# Shruthi-Digital-XT-v03.net
KiCad netlist of a schematic drawn in EAGLE
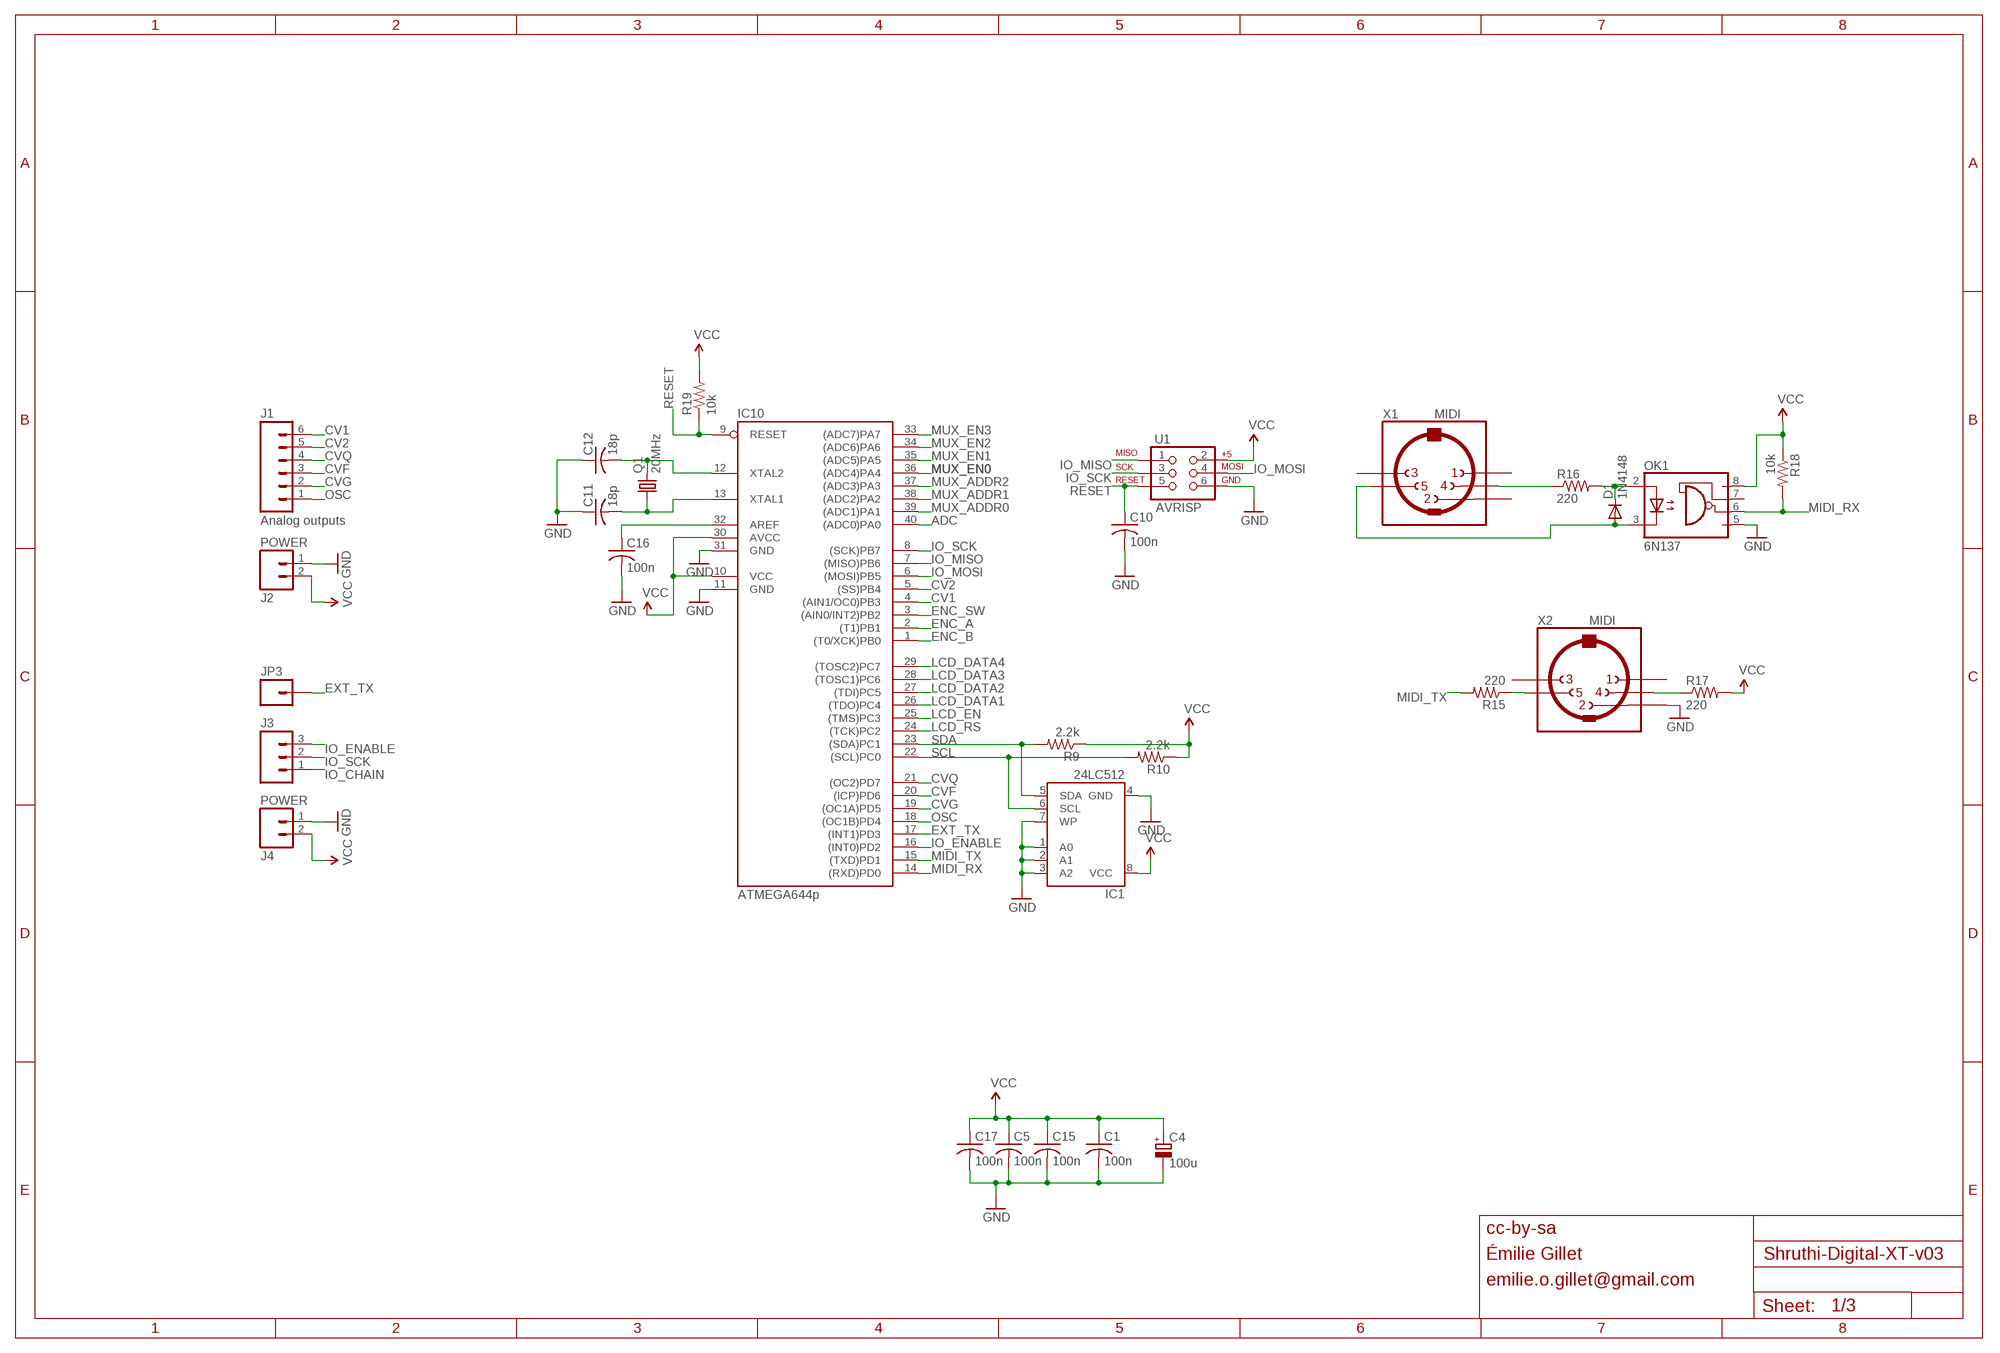
[diagram p0: schematic, sheet 1]
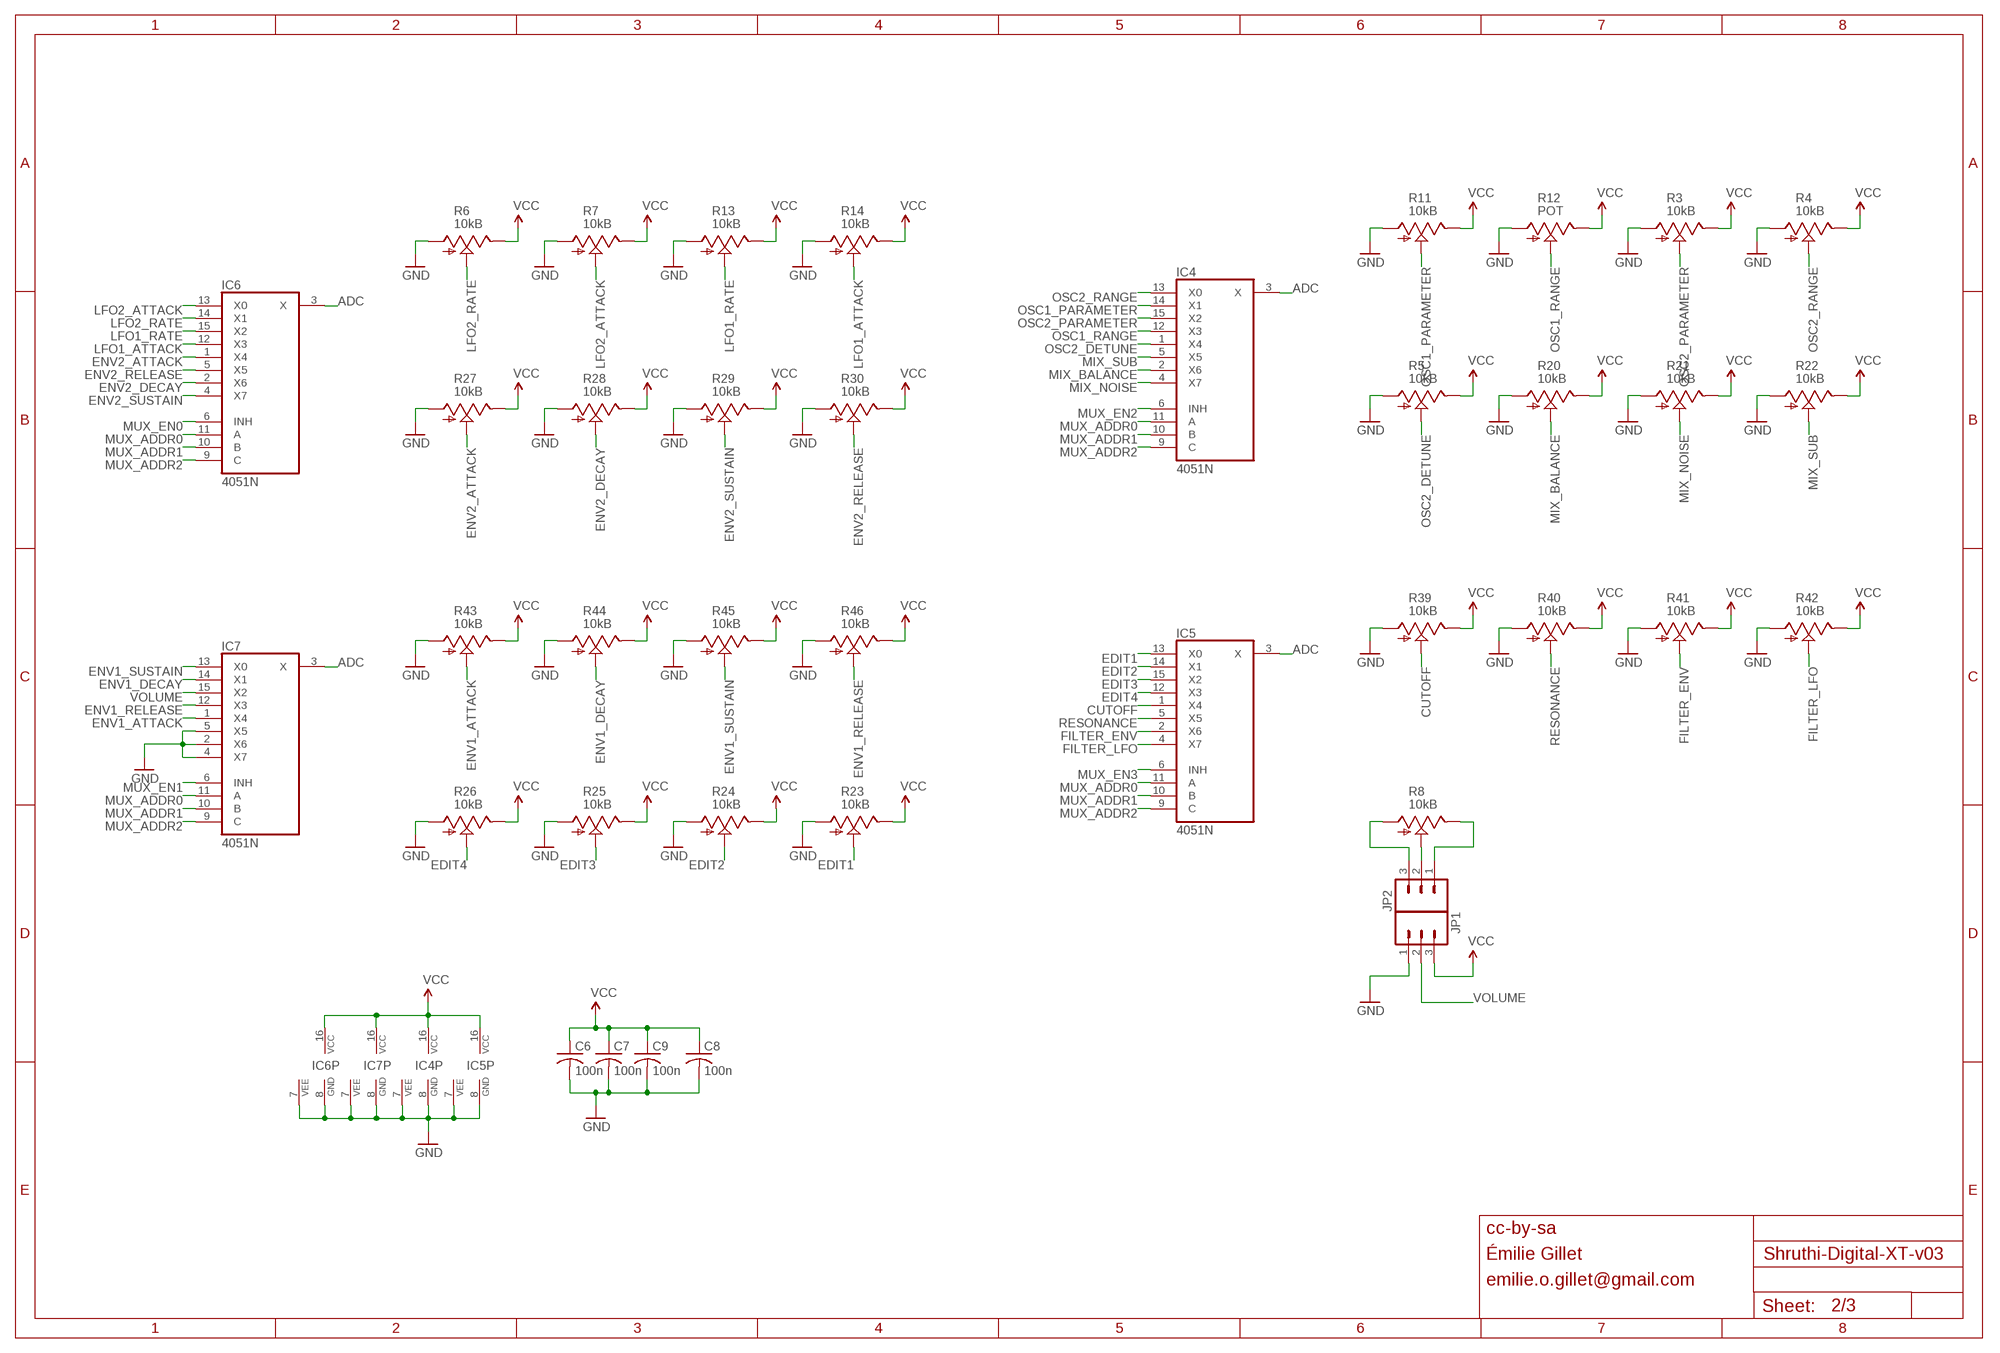
[diagram p1: schematic, sheet 2]
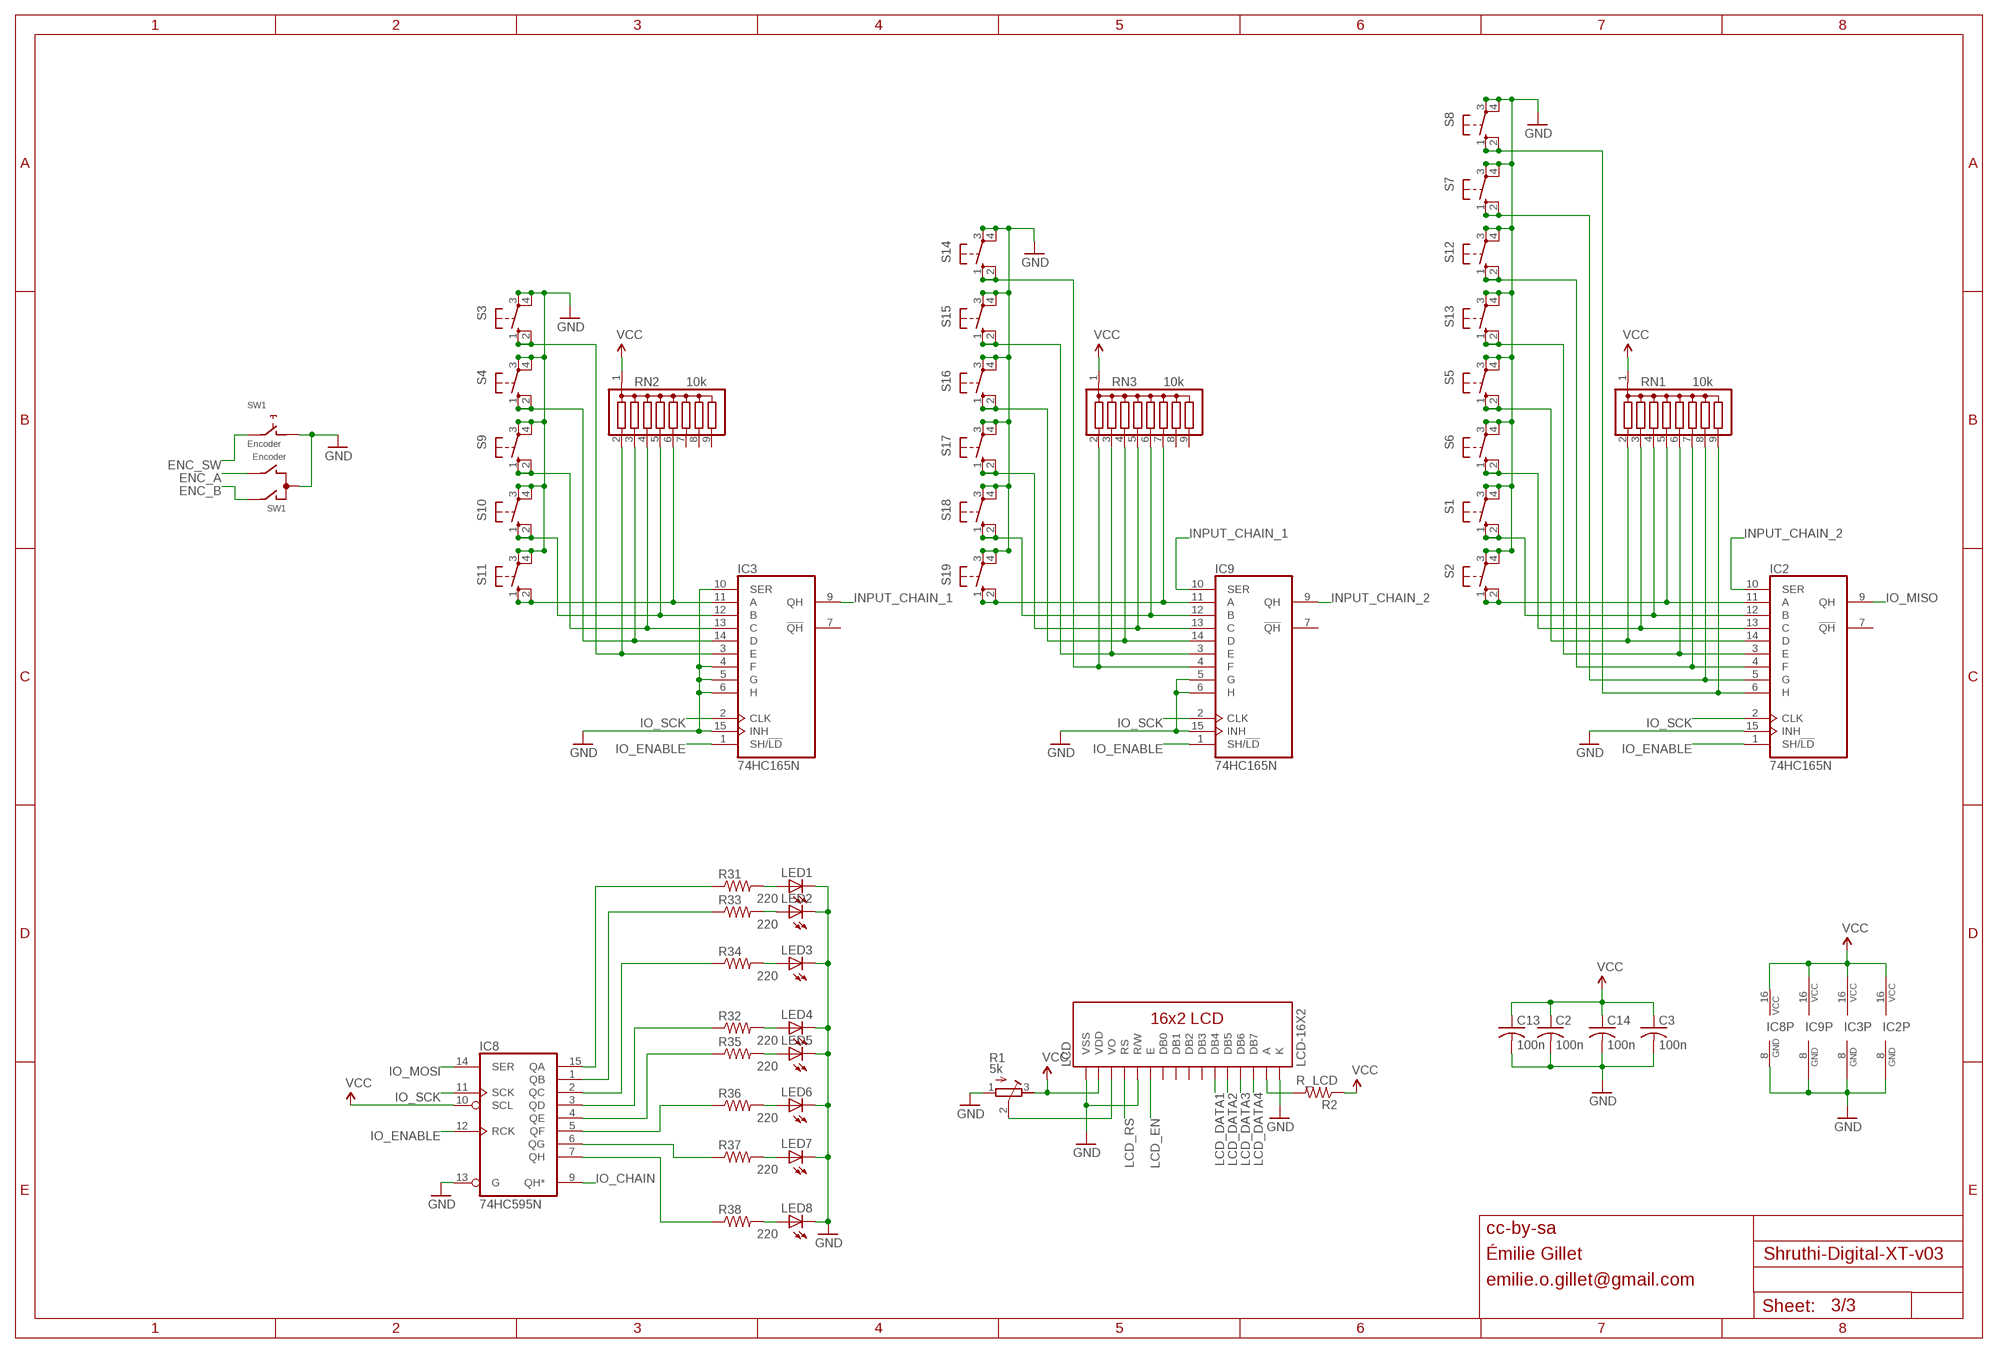
[diagram p2: schematic, sheet 3]

(export (version "E")
  (design (tool "Eeschema 10.0.6"))
  (components
    (comp (ref "C1")
      (value "100n")
      (footprint "eagle-import:C025-024X044")
      (libsource (lib "eagle-import") (part "C-US025-024X044"))
    )
    (comp (ref "C4")
      (value "100u")
      (footprint "eagle-import:E2,5-7")
      (libsource (lib "eagle-import") (part "CPOL-EUE2.5-7"))
    )
    (comp (ref "C5")
      (value "100n")
      (footprint "eagle-import:C025-024X044")
      (libsource (lib "eagle-import") (part "C-US025-024X044"))
    )
    (comp (ref "C10")
      (value "100n")
      (footprint "eagle-import:C025-024X044")
      (libsource (lib "eagle-import") (part "C-US025-024X044"))
    )
    (comp (ref "C11")
      (value "18p")
      (footprint "eagle-import:C025-024X044")
      (libsource (lib "eagle-import") (part "C-US025-024X044"))
    )
    (comp (ref "C12")
      (value "18p")
      (footprint "eagle-import:C025-024X044")
      (libsource (lib "eagle-import") (part "C-US025-024X044"))
    )
    (comp (ref "C15")
      (value "100n")
      (footprint "eagle-import:C025-024X044")
      (libsource (lib "eagle-import") (part "C-US025-024X044"))
    )
    (comp (ref "C16")
      (value "100n")
      (footprint "eagle-import:C025-024X044")
      (libsource (lib "eagle-import") (part "C-US025-024X044"))
    )
    (comp (ref "C17")
      (value "100n")
      (footprint "eagle-import:C025-024X044")
      (libsource (lib "eagle-import") (part "C-US025-024X044"))
    )
    (comp (ref "D1")
      (value "1N4148")
      (footprint "eagle-import:D-5")
      (libsource (lib "eagle-import") (part "DIODE-D-5"))
    )
    (comp (ref "IC1")
      (value "24LC512")
      (footprint "eagle-import:DIL08")
      (libsource (lib "eagle-import") (part "AT24CP"))
    )
    (comp (ref "IC10")
      (value "ATMEGA644p")
      (footprint "eagle-import:DIL40")
      (libsource (lib "eagle-import") (part "MEGA16-P"))
    )
    (comp (ref "J1")
      (value "M06SIP")
      (footprint "eagle-import:1X06")
      (libsource (lib "eagle-import") (part "M06SIP"))
    )
    (comp (ref "J2")
      (value "POWER")
      (footprint "eagle-import:1X02")
      (libsource (lib "eagle-import") (part "M02PTH"))
    )
    (comp (ref "J3")
      (value "M03PTH")
      (footprint "eagle-import:1X03")
      (libsource (lib "eagle-import") (part "M03PTH"))
    )
    (comp (ref "J4")
      (value "POWER")
      (footprint "eagle-import:1X02")
      (libsource (lib "eagle-import") (part "M02PTH"))
    )
    (comp (ref "JP3")
      (value "M01PTH")
      (footprint "eagle-import:1X01")
      (libsource (lib "eagle-import") (part "M01PTH"))
    )
    (comp (ref "OK1")
      (value "6N137")
      (footprint "eagle-import:DIL08")
      (libsource (lib "eagle-import") (part "6N137"))
    )
    (comp (ref "Q1")
      (value "20MHz")
      (footprint "eagle-import:HC49U-V")
      (libsource (lib "eagle-import") (part "CRYSTALHC49U-V"))
    )
    (comp (ref "R9")
      (value "2.2k")
      (footprint "eagle-import:0204_7")
      (libsource (lib "eagle-import") (part "R-US_0204/7"))
    )
    (comp (ref "R10")
      (value "2.2k")
      (footprint "eagle-import:0204_7")
      (libsource (lib "eagle-import") (part "R-US_0204/7"))
    )
    (comp (ref "R15")
      (value "220")
      (footprint "eagle-import:0204_7")
      (libsource (lib "eagle-import") (part "R-US_0204/7"))
    )
    (comp (ref "R16")
      (value "220")
      (footprint "eagle-import:0204_7")
      (libsource (lib "eagle-import") (part "R-US_0204/7"))
    )
    (comp (ref "R17")
      (value "220")
      (footprint "eagle-import:0204_7")
      (libsource (lib "eagle-import") (part "R-US_0204/7"))
    )
    (comp (ref "R18")
      (value "10k")
      (footprint "eagle-import:0204_7")
      (libsource (lib "eagle-import") (part "R-US_0204/7"))
    )
    (comp (ref "R19")
      (value "10k")
      (footprint "eagle-import:0204_7")
      (libsource (lib "eagle-import") (part "R-US_0204/7"))
    )
    (comp (ref "U1")
      (value "AVRISP")
      (footprint "eagle-import:2X3")
      (libsource (lib "eagle-import") (part "AVR_SPI_PRG_6PTH"))
    )
    (comp (ref "X1")
      (value "MIDI")
      (footprint "eagle-import:MAB5SH")
      (libsource (lib "eagle-import") (part "MAB5SH"))
    )
    (comp (ref "X2")
      (value "MIDI")
      (footprint "eagle-import:MAB5SH")
      (libsource (lib "eagle-import") (part "MAB5SH"))
    )
    (comp (ref "C2")
      (value "100n")
      (footprint "eagle-import:C025-024X044")
      (libsource (lib "eagle-import") (part "C-US025-024X044"))
    )
    (comp (ref "C3")
      (value "100n")
      (footprint "eagle-import:C025-024X044")
      (libsource (lib "eagle-import") (part "C-US025-024X044"))
    )
    (comp (ref "C13")
      (value "100n")
      (footprint "eagle-import:C025-024X044")
      (libsource (lib "eagle-import") (part "C-US025-024X044"))
    )
    (comp (ref "C14")
      (value "100n")
      (footprint "eagle-import:C025-024X044")
      (libsource (lib "eagle-import") (part "C-US025-024X044"))
    )
    (comp (ref "IC2")
      (value "74HC165N")
      (footprint "eagle-import:DIL16")
      (libsource (lib "eagle-import") (part "74165NLS"))
    )
    (comp (ref "IC3")
      (value "74HC165N")
      (footprint "eagle-import:DIL16")
      (libsource (lib "eagle-import") (part "74165NLS"))
    )
    (comp (ref "IC8")
      (value "74HC595N")
      (footprint "eagle-import:DIL16")
      (libsource (lib "eagle-import") (part "74595NHC"))
    )
    (comp (ref "IC9")
      (value "74HC165N")
      (footprint "eagle-import:DIL16")
      (libsource (lib "eagle-import") (part "74165NLS"))
    )
    (comp (ref "LCD")
      (value "LCD-16X2")
      (footprint "eagle-import:LCD-16X2")
      (libsource (lib "eagle-import") (part "LCD-16X2"))
    )
    (comp (ref "LED1")
      (value "LED3MM")
      (footprint "eagle-import:LED3MM")
      (libsource (lib "eagle-import") (part "LED3MM"))
    )
    (comp (ref "LED2")
      (value "LED3MM")
      (footprint "eagle-import:LED3MM")
      (libsource (lib "eagle-import") (part "LED3MM"))
    )
    (comp (ref "LED3")
      (value "LED3MM")
      (footprint "eagle-import:LED3MM")
      (libsource (lib "eagle-import") (part "LED3MM"))
    )
    (comp (ref "LED4")
      (value "LED3MM")
      (footprint "eagle-import:LED3MM")
      (libsource (lib "eagle-import") (part "LED3MM"))
    )
    (comp (ref "LED5")
      (value "LED3MM")
      (footprint "eagle-import:LED3MM")
      (libsource (lib "eagle-import") (part "LED3MM"))
    )
    (comp (ref "LED6")
      (value "LED3MM")
      (footprint "eagle-import:LED3MM")
      (libsource (lib "eagle-import") (part "LED3MM"))
    )
    (comp (ref "LED7")
      (value "LED3MM")
      (footprint "eagle-import:LED3MM")
      (libsource (lib "eagle-import") (part "LED3MM"))
    )
    (comp (ref "LED8")
      (value "LED3MM")
      (footprint "eagle-import:LED3MM")
      (libsource (lib "eagle-import") (part "LED3MM"))
    )
    (comp (ref "R1")
      (value "5k")
      (footprint "eagle-import:RTRIM3339P")
      (libsource (lib "eagle-import") (part "R-TRIMM3339P"))
    )
    (comp (ref "R2")
      (value "R_LCD")
      (footprint "eagle-import:0204_7")
      (libsource (lib "eagle-import") (part "R-US_0204/7"))
    )
    (comp (ref "R31")
      (value "220")
      (footprint "eagle-import:0204_7")
      (libsource (lib "eagle-import") (part "R-US_0204/7"))
    )
    (comp (ref "R32")
      (value "220")
      (footprint "eagle-import:0204_7")
      (libsource (lib "eagle-import") (part "R-US_0204/7"))
    )
    (comp (ref "R33")
      (value "220")
      (footprint "eagle-import:0204_7")
      (libsource (lib "eagle-import") (part "R-US_0204/7"))
    )
    (comp (ref "R34")
      (value "220")
      (footprint "eagle-import:0204_7")
      (libsource (lib "eagle-import") (part "R-US_0204/7"))
    )
    (comp (ref "R35")
      (value "220")
      (footprint "eagle-import:0204_7")
      (libsource (lib "eagle-import") (part "R-US_0204/7"))
    )
    (comp (ref "R36")
      (value "220")
      (footprint "eagle-import:0204_7")
      (libsource (lib "eagle-import") (part "R-US_0204/7"))
    )
    (comp (ref "R37")
      (value "220")
      (footprint "eagle-import:0204_7")
      (libsource (lib "eagle-import") (part "R-US_0204/7"))
    )
    (comp (ref "R38")
      (value "220")
      (footprint "eagle-import:0204_7")
      (libsource (lib "eagle-import") (part "R-US_0204/7"))
    )
    (comp (ref "RN1")
      (value "10k")
      (footprint "eagle-import:SIL9")
      (libsource (lib "eagle-import") (part "G08R"))
    )
    (comp (ref "RN2")
      (value "10k")
      (footprint "eagle-import:SIL9")
      (libsource (lib "eagle-import") (part "G08R"))
    )
    (comp (ref "RN3")
      (value "10k")
      (footprint "eagle-import:SIL9")
      (libsource (lib "eagle-import") (part "G08R"))
    )
    (comp (ref "S1")
      (value "40-XX")
      (footprint "eagle-import:B3F-40XX")
      (libsource (lib "eagle-import") (part "40-XX"))
    )
    (comp (ref "S2")
      (value "40-XX")
      (footprint "eagle-import:B3F-40XX")
      (libsource (lib "eagle-import") (part "40-XX"))
    )
    (comp (ref "S3")
      (value "40-XX")
      (footprint "eagle-import:B3F-40XX")
      (libsource (lib "eagle-import") (part "40-XX"))
    )
    (comp (ref "S4")
      (value "40-XX")
      (footprint "eagle-import:B3F-40XX")
      (libsource (lib "eagle-import") (part "40-XX"))
    )
    (comp (ref "S5")
      (value "40-XX")
      (footprint "eagle-import:B3F-40XX")
      (libsource (lib "eagle-import") (part "40-XX"))
    )
    (comp (ref "S6")
      (value "40-XX")
      (footprint "eagle-import:B3F-40XX")
      (libsource (lib "eagle-import") (part "40-XX"))
    )
    (comp (ref "S7")
      (value "40-XX")
      (footprint "eagle-import:B3F-40XX")
      (libsource (lib "eagle-import") (part "40-XX"))
    )
    (comp (ref "S8")
      (value "40-XX")
      (footprint "eagle-import:B3F-40XX")
      (libsource (lib "eagle-import") (part "40-XX"))
    )
    (comp (ref "S9")
      (value "40-XX")
      (footprint "eagle-import:B3F-40XX")
      (libsource (lib "eagle-import") (part "40-XX"))
    )
    (comp (ref "S10")
      (value "40-XX")
      (footprint "eagle-import:B3F-40XX")
      (libsource (lib "eagle-import") (part "40-XX"))
    )
    (comp (ref "S11")
      (value "40-XX")
      (footprint "eagle-import:B3F-40XX")
      (libsource (lib "eagle-import") (part "40-XX"))
    )
    (comp (ref "S12")
      (value "40-XX")
      (footprint "eagle-import:B3F-40XX")
      (libsource (lib "eagle-import") (part "40-XX"))
    )
    (comp (ref "S13")
      (value "40-XX")
      (footprint "eagle-import:B3F-40XX")
      (libsource (lib "eagle-import") (part "40-XX"))
    )
    (comp (ref "S14")
      (value "40-XX")
      (footprint "eagle-import:B3F-40XX")
      (libsource (lib "eagle-import") (part "40-XX"))
    )
    (comp (ref "S15")
      (value "40-XX")
      (footprint "eagle-import:B3F-40XX")
      (libsource (lib "eagle-import") (part "40-XX"))
    )
    (comp (ref "S16")
      (value "40-XX")
      (footprint "eagle-import:B3F-40XX")
      (libsource (lib "eagle-import") (part "40-XX"))
    )
    (comp (ref "S17")
      (value "40-XX")
      (footprint "eagle-import:B3F-40XX")
      (libsource (lib "eagle-import") (part "40-XX"))
    )
    (comp (ref "S18")
      (value "40-XX")
      (footprint "eagle-import:B3F-40XX")
      (libsource (lib "eagle-import") (part "40-XX"))
    )
    (comp (ref "S19")
      (value "40-XX")
      (footprint "eagle-import:B3F-40XX")
      (libsource (lib "eagle-import") (part "40-XX"))
    )
    (comp (ref "SW1")
      (value "Encoder")
      (footprint "eagle-import:ALPS_EC12E_SW")
      (libsource (lib "eagle-import") (part "EC12E_SW"))
    )
    (comp (ref "C6")
      (value "100n")
      (footprint "eagle-import:C025-024X044")
      (libsource (lib "eagle-import") (part "C-US025-024X044"))
    )
    (comp (ref "C7")
      (value "100n")
      (footprint "eagle-import:C025-024X044")
      (libsource (lib "eagle-import") (part "C-US025-024X044"))
    )
    (comp (ref "C8")
      (value "100n")
      (footprint "eagle-import:C025-024X044")
      (libsource (lib "eagle-import") (part "C-US025-024X044"))
    )
    (comp (ref "C9")
      (value "100n")
      (footprint "eagle-import:C025-024X044")
      (libsource (lib "eagle-import") (part "C-US025-024X044"))
    )
    (comp (ref "IC4")
      (value "4051N")
      (footprint "eagle-import:DIL16")
      (libsource (lib "eagle-import") (part "4051N"))
    )
    (comp (ref "IC5")
      (value "4051N")
      (footprint "eagle-import:DIL16")
      (libsource (lib "eagle-import") (part "4051N"))
    )
    (comp (ref "IC6")
      (value "4051N")
      (footprint "eagle-import:DIL16")
      (libsource (lib "eagle-import") (part "4051N"))
    )
    (comp (ref "IC7")
      (value "4051N")
      (footprint "eagle-import:DIL16")
      (libsource (lib "eagle-import") (part "4051N"))
    )
    (comp (ref "JP1")
      (value "M03PTH")
      (footprint "eagle-import:1X03")
      (libsource (lib "eagle-import") (part "M03PTH"))
    )
    (comp (ref "JP2")
      (value "M03PTH")
      (footprint "eagle-import:1X03")
      (libsource (lib "eagle-import") (part "M03PTH"))
    )
    (comp (ref "R3")
      (value "10kB")
      (footprint "eagle-import:ALPS_POT_VERTICAL")
      (libsource (lib "eagle-import") (part "POT_USVERTICAL"))
    )
    (comp (ref "R4")
      (value "10kB")
      (footprint "eagle-import:ALPS_POT_VERTICAL")
      (libsource (lib "eagle-import") (part "POT_USVERTICAL"))
    )
    (comp (ref "R5")
      (value "10kB")
      (footprint "eagle-import:ALPS_POT_VERTICAL")
      (libsource (lib "eagle-import") (part "POT_USVERTICAL"))
    )
    (comp (ref "R6")
      (value "10kB")
      (footprint "eagle-import:ALPS_POT_VERTICAL")
      (libsource (lib "eagle-import") (part "POT_USVERTICAL"))
    )
    (comp (ref "R7")
      (value "10kB")
      (footprint "eagle-import:ALPS_POT_VERTICAL")
      (libsource (lib "eagle-import") (part "POT_USVERTICAL"))
    )
    (comp (ref "R8")
      (value "10kB")
      (footprint "eagle-import:ALPS_POT_VERTICAL")
      (libsource (lib "eagle-import") (part "POT_USVERTICAL"))
    )
    (comp (ref "R11")
      (value "10kB")
      (footprint "eagle-import:ALPS_POT_VERTICAL")
      (libsource (lib "eagle-import") (part "POT_USVERTICAL"))
    )
    (comp (ref "R12")
      (value "POT")
      (footprint "eagle-import:ALPS_POT_VERTICAL")
      (libsource (lib "eagle-import") (part "POT_USVERTICAL"))
    )
    (comp (ref "R13")
      (value "10kB")
      (footprint "eagle-import:ALPS_POT_VERTICAL")
      (libsource (lib "eagle-import") (part "POT_USVERTICAL"))
    )
    (comp (ref "R14")
      (value "10kB")
      (footprint "eagle-import:ALPS_POT_VERTICAL")
      (libsource (lib "eagle-import") (part "POT_USVERTICAL"))
    )
    (comp (ref "R20")
      (value "10kB")
      (footprint "eagle-import:ALPS_POT_VERTICAL")
      (libsource (lib "eagle-import") (part "POT_USVERTICAL"))
    )
    (comp (ref "R21")
      (value "10kB")
      (footprint "eagle-import:ALPS_POT_VERTICAL")
      (libsource (lib "eagle-import") (part "POT_USVERTICAL"))
    )
    (comp (ref "R22")
      (value "10kB")
      (footprint "eagle-import:ALPS_POT_VERTICAL")
      (libsource (lib "eagle-import") (part "POT_USVERTICAL"))
    )
    (comp (ref "R23")
      (value "10kB")
      (footprint "eagle-import:ALPS_POT_VERTICAL")
      (libsource (lib "eagle-import") (part "POT_USVERTICAL"))
    )
    (comp (ref "R24")
      (value "10kB")
      (footprint "eagle-import:ALPS_POT_VERTICAL")
      (libsource (lib "eagle-import") (part "POT_USVERTICAL"))
    )
    (comp (ref "R25")
      (value "10kB")
      (footprint "eagle-import:ALPS_POT_VERTICAL")
      (libsource (lib "eagle-import") (part "POT_USVERTICAL"))
    )
    (comp (ref "R26")
      (value "10kB")
      (footprint "eagle-import:ALPS_POT_VERTICAL")
      (libsource (lib "eagle-import") (part "POT_USVERTICAL"))
    )
    (comp (ref "R27")
      (value "10kB")
      (footprint "eagle-import:ALPS_POT_VERTICAL")
      (libsource (lib "eagle-import") (part "POT_USVERTICAL"))
    )
    (comp (ref "R28")
      (value "10kB")
      (footprint "eagle-import:ALPS_POT_VERTICAL")
      (libsource (lib "eagle-import") (part "POT_USVERTICAL"))
    )
    (comp (ref "R29")
      (value "10kB")
      (footprint "eagle-import:ALPS_POT_VERTICAL")
      (libsource (lib "eagle-import") (part "POT_USVERTICAL"))
    )
    (comp (ref "R30")
      (value "10kB")
      (footprint "eagle-import:ALPS_POT_VERTICAL")
      (libsource (lib "eagle-import") (part "POT_USVERTICAL"))
    )
    (comp (ref "R39")
      (value "10kB")
      (footprint "eagle-import:ALPS_POT_VERTICAL")
      (libsource (lib "eagle-import") (part "POT_USVERTICAL"))
    )
    (comp (ref "R40")
      (value "10kB")
      (footprint "eagle-import:ALPS_POT_VERTICAL")
      (libsource (lib "eagle-import") (part "POT_USVERTICAL"))
    )
    (comp (ref "R41")
      (value "10kB")
      (footprint "eagle-import:ALPS_POT_VERTICAL")
      (libsource (lib "eagle-import") (part "POT_USVERTICAL"))
    )
    (comp (ref "R42")
      (value "10kB")
      (footprint "eagle-import:ALPS_POT_VERTICAL")
      (libsource (lib "eagle-import") (part "POT_USVERTICAL"))
    )
    (comp (ref "R43")
      (value "10kB")
      (footprint "eagle-import:ALPS_POT_VERTICAL")
      (libsource (lib "eagle-import") (part "POT_USVERTICAL"))
    )
    (comp (ref "R44")
      (value "10kB")
      (footprint "eagle-import:ALPS_POT_VERTICAL")
      (libsource (lib "eagle-import") (part "POT_USVERTICAL"))
    )
    (comp (ref "R45")
      (value "10kB")
      (footprint "eagle-import:ALPS_POT_VERTICAL")
      (libsource (lib "eagle-import") (part "POT_USVERTICAL"))
    )
    (comp (ref "R46")
      (value "10kB")
      (footprint "eagle-import:ALPS_POT_VERTICAL")
      (libsource (lib "eagle-import") (part "POT_USVERTICAL"))
    )
  )
  (nets
    (net (code "1") (name "ADC") (class "Default")
      (node (ref "IC10") (pin "40") (pinfunction "(ADC0)PA0_40") (pintype "bidirectional"))
      (node (ref "IC4") (pin "3") (pinfunction "X_3") (pintype "bidirectional"))
      (node (ref "IC5") (pin "3") (pinfunction "X_3") (pintype "bidirectional"))
      (node (ref "IC6") (pin "3") (pinfunction "X_3") (pintype "bidirectional"))
      (node (ref "IC7") (pin "3") (pinfunction "X_3") (pintype "bidirectional"))
    )
    (net (code "2") (name "CUTOFF") (class "Default")
      (node (ref "IC5") (pin "1") (pinfunction "X4_1") (pintype "bidirectional"))
      (node (ref "R39") (pin "P$2") (pinfunction "S_P$2") (pintype "passive"))
    )
    (net (code "3") (name "CV1") (class "Default")
      (node (ref "IC10") (pin "4") (pinfunction "(AIN1/OC0)PB3_4") (pintype "bidirectional"))
      (node (ref "J1") (pin "6") (pinfunction "6_6") (pintype "passive"))
    )
    (net (code "4") (name "CV2") (class "Default")
      (node (ref "IC10") (pin "5") (pinfunction "(SS)PB4_5") (pintype "bidirectional"))
      (node (ref "J1") (pin "5") (pinfunction "5_5") (pintype "passive"))
    )
    (net (code "5") (name "CVF") (class "Default")
      (node (ref "IC10") (pin "20") (pinfunction "(ICP)PD6_20") (pintype "bidirectional"))
      (node (ref "J1") (pin "3") (pinfunction "3_3") (pintype "passive"))
    )
    (net (code "6") (name "CVG") (class "Default")
      (node (ref "IC10") (pin "19") (pinfunction "(OC1A)PD5_19") (pintype "bidirectional"))
      (node (ref "J1") (pin "2") (pinfunction "2_2") (pintype "passive"))
    )
    (net (code "7") (name "CVQ") (class "Default")
      (node (ref "IC10") (pin "21") (pinfunction "(OC2)PD7_21") (pintype "bidirectional"))
      (node (ref "J1") (pin "4") (pinfunction "4_4") (pintype "passive"))
    )
    (net (code "8") (name "EDIT1") (class "Default")
      (node (ref "IC5") (pin "13") (pinfunction "X0_13") (pintype "bidirectional"))
      (node (ref "R23") (pin "P$2") (pinfunction "S_P$2") (pintype "passive"))
    )
    (net (code "9") (name "EDIT2") (class "Default")
      (node (ref "IC5") (pin "14") (pinfunction "X1_14") (pintype "bidirectional"))
      (node (ref "R24") (pin "P$2") (pinfunction "S_P$2") (pintype "passive"))
    )
    (net (code "10") (name "EDIT3") (class "Default")
      (node (ref "IC5") (pin "15") (pinfunction "X2_15") (pintype "bidirectional"))
      (node (ref "R25") (pin "P$2") (pinfunction "S_P$2") (pintype "passive"))
    )
    (net (code "11") (name "EDIT4") (class "Default")
      (node (ref "IC5") (pin "12") (pinfunction "X3_12") (pintype "bidirectional"))
      (node (ref "R26") (pin "P$2") (pinfunction "S_P$2") (pintype "passive"))
    )
    (net (code "12") (name "ENC_A") (class "Default")
      (node (ref "IC10") (pin "2") (pinfunction "(T1)PB1_2") (pintype "bidirectional"))
      (node (ref "SW1") (pin "B") (pinfunction "B_B") (pintype "passive"))
    )
    (net (code "13") (name "ENC_B") (class "Default")
      (node (ref "IC10") (pin "1") (pinfunction "(T0/XCK)PB0_1") (pintype "bidirectional"))
      (node (ref "SW1") (pin "A") (pinfunction "A_A") (pintype "passive"))
    )
    (net (code "14") (name "ENC_SW") (class "Default")
      (node (ref "IC10") (pin "3") (pinfunction "(AIN0/INT2)PB2_3") (pintype "bidirectional"))
      (node (ref "SW1") (pin "E") (pinfunction "2_E") (pintype "passive"))
    )
    (net (code "15") (name "ENV1_ATTACK") (class "Default")
      (node (ref "IC7") (pin "1") (pinfunction "X4_1") (pintype "bidirectional"))
      (node (ref "R43") (pin "P$2") (pinfunction "S_P$2") (pintype "passive"))
    )
    (net (code "16") (name "ENV1_DECAY") (class "Default")
      (node (ref "IC7") (pin "14") (pinfunction "X1_14") (pintype "bidirectional"))
      (node (ref "R44") (pin "P$2") (pinfunction "S_P$2") (pintype "passive"))
    )
    (net (code "17") (name "ENV1_RELEASE") (class "Default")
      (node (ref "IC7") (pin "12") (pinfunction "X3_12") (pintype "bidirectional"))
      (node (ref "R46") (pin "P$2") (pinfunction "S_P$2") (pintype "passive"))
    )
    (net (code "18") (name "ENV1_SUSTAIN") (class "Default")
      (node (ref "IC7") (pin "13") (pinfunction "X0_13") (pintype "bidirectional"))
      (node (ref "R45") (pin "P$2") (pinfunction "S_P$2") (pintype "passive"))
    )
    (net (code "19") (name "ENV2_ATTACK") (class "Default")
      (node (ref "IC6") (pin "1") (pinfunction "X4_1") (pintype "bidirectional"))
      (node (ref "R27") (pin "P$2") (pinfunction "S_P$2") (pintype "passive"))
    )
    (net (code "20") (name "ENV2_DECAY") (class "Default")
      (node (ref "IC6") (pin "2") (pinfunction "X6_2") (pintype "bidirectional"))
      (node (ref "R28") (pin "P$2") (pinfunction "S_P$2") (pintype "passive"))
    )
    (net (code "21") (name "ENV2_RELEASE") (class "Default")
      (node (ref "IC6") (pin "5") (pinfunction "X5_5") (pintype "bidirectional"))
      (node (ref "R30") (pin "P$2") (pinfunction "S_P$2") (pintype "passive"))
    )
    (net (code "22") (name "ENV2_SUSTAIN") (class "Default")
      (node (ref "IC6") (pin "4") (pinfunction "X7_4") (pintype "bidirectional"))
      (node (ref "R29") (pin "P$2") (pinfunction "S_P$2") (pintype "passive"))
    )
    (net (code "23") (name "EXT_TX") (class "Default")
      (node (ref "IC10") (pin "17") (pinfunction "(INT1)PD3_17") (pintype "bidirectional"))
      (node (ref "JP3") (pin "1") (pinfunction "1_1") (pintype "passive"))
    )
    (net (code "24") (name "FILTER_ENV") (class "Default")
      (node (ref "IC5") (pin "2") (pinfunction "X6_2") (pintype "bidirectional"))
      (node (ref "R41") (pin "P$2") (pinfunction "S_P$2") (pintype "passive"))
    )
    (net (code "25") (name "FILTER_LFO") (class "Default")
      (node (ref "IC5") (pin "4") (pinfunction "X7_4") (pintype "bidirectional"))
      (node (ref "R42") (pin "P$2") (pinfunction "S_P$2") (pintype "passive"))
    )
    (net (code "26") (name "GND") (class "Default")
      (node (ref "C1") (pin "2") (pinfunction "2_2") (pintype "passive"))
      (node (ref "C10") (pin "2") (pinfunction "2_2") (pintype "passive"))
      (node (ref "C11") (pin "1") (pinfunction "1_1") (pintype "passive"))
      (node (ref "C12") (pin "1") (pinfunction "1_1") (pintype "passive"))
      (node (ref "C13") (pin "2") (pinfunction "2_2") (pintype "passive"))
      (node (ref "C14") (pin "2") (pinfunction "2_2") (pintype "passive"))
      (node (ref "C15") (pin "2") (pinfunction "2_2") (pintype "passive"))
      (node (ref "C16") (pin "2") (pinfunction "2_2") (pintype "passive"))
      (node (ref "C17") (pin "2") (pinfunction "2_2") (pintype "passive"))
      (node (ref "C2") (pin "2") (pinfunction "2_2") (pintype "passive"))
      (node (ref "C3") (pin "2") (pinfunction "2_2") (pintype "passive"))
      (node (ref "C4") (pin "-") (pinfunction "-_-") (pintype "passive"))
      (node (ref "C5") (pin "2") (pinfunction "2_2") (pintype "passive"))
      (node (ref "C6") (pin "2") (pinfunction "2_2") (pintype "passive"))
      (node (ref "C7") (pin "2") (pinfunction "2_2") (pintype "passive"))
      (node (ref "C8") (pin "2") (pinfunction "2_2") (pintype "passive"))
      (node (ref "C9") (pin "2") (pinfunction "2_2") (pintype "passive"))
      (node (ref "IC1") (pin "1") (pinfunction "A0_1") (pintype "input"))
      (node (ref "IC1") (pin "2") (pinfunction "A1_2") (pintype "input"))
      (node (ref "IC1") (pin "3") (pinfunction "A2_3") (pintype "input"))
      (node (ref "IC1") (pin "4") (pinfunction "GND_4") (pintype "power_in"))
      (node (ref "IC1") (pin "7") (pinfunction "WP_7") (pintype "input"))
      (node (ref "IC10") (pin "11") (pinfunction "GND_11") (pintype "power_in"))
      (node (ref "IC10") (pin "31") (pinfunction "GND_31") (pintype "power_in"))
      (node (ref "IC2") (pin "15") (pinfunction "INH_15") (pintype "input"))
      (node (ref "IC2") (pin "8") (pinfunction "GND_8") (pintype "power_in"))
      (node (ref "IC3") (pin "10") (pinfunction "SER_10") (pintype "input"))
      (node (ref "IC3") (pin "15") (pinfunction "INH_15") (pintype "input"))
      (node (ref "IC3") (pin "4") (pinfunction "F_4") (pintype "input"))
      (node (ref "IC3") (pin "5") (pinfunction "G_5") (pintype "input"))
      (node (ref "IC3") (pin "6") (pinfunction "H_6") (pintype "input"))
      (node (ref "IC3") (pin "8") (pinfunction "GND_8") (pintype "power_in"))
      (node (ref "IC4") (pin "7") (pinfunction "VEE_7") (pintype "power_in"))
      (node (ref "IC4") (pin "8") (pinfunction "GND_8") (pintype "power_in"))
      (node (ref "IC5") (pin "7") (pinfunction "VEE_7") (pintype "power_in"))
      (node (ref "IC5") (pin "8") (pinfunction "GND_8") (pintype "power_in"))
      (node (ref "IC6") (pin "7") (pinfunction "VEE_7") (pintype "power_in"))
      (node (ref "IC6") (pin "8") (pinfunction "GND_8") (pintype "power_in"))
      (node (ref "IC7") (pin "2") (pinfunction "X6_2") (pintype "bidirectional"))
      (node (ref "IC7") (pin "4") (pinfunction "X7_4") (pintype "bidirectional"))
      (node (ref "IC7") (pin "5") (pinfunction "X5_5") (pintype "bidirectional"))
      (node (ref "IC7") (pin "7") (pinfunction "VEE_7") (pintype "power_in"))
      (node (ref "IC7") (pin "8") (pinfunction "GND_8") (pintype "power_in"))
      (node (ref "IC8") (pin "13") (pinfunction "G_13") (pintype "input"))
      (node (ref "IC8") (pin "8") (pinfunction "GND_8") (pintype "power_in"))
      (node (ref "IC9") (pin "15") (pinfunction "INH_15") (pintype "input"))
      (node (ref "IC9") (pin "5") (pinfunction "G_5") (pintype "input"))
      (node (ref "IC9") (pin "6") (pinfunction "H_6") (pintype "input"))
      (node (ref "IC9") (pin "8") (pinfunction "GND_8") (pintype "power_in"))
      (node (ref "J2") (pin "1") (pinfunction "1_1") (pintype "passive"))
      (node (ref "J4") (pin "1") (pinfunction "1_1") (pintype "passive"))
      (node (ref "JP1") (pin "1") (pinfunction "1_1") (pintype "passive"))
      (node (ref "LCD") (pin "1") (pinfunction "VSS_1") (pintype "power_in"))
      (node (ref "LCD") (pin "16") (pinfunction "K_16") (pintype "power_in"))
      (node (ref "LCD") (pin "5") (pinfunction "R/W_5") (pintype "input"))
      (node (ref "LED1") (pin "K") (pinfunction "C_K") (pintype "passive"))
      (node (ref "LED2") (pin "K") (pinfunction "C_K") (pintype "passive"))
      (node (ref "LED3") (pin "K") (pinfunction "C_K") (pintype "passive"))
      (node (ref "LED4") (pin "K") (pinfunction "C_K") (pintype "passive"))
      (node (ref "LED5") (pin "K") (pinfunction "C_K") (pintype "passive"))
      (node (ref "LED6") (pin "K") (pinfunction "C_K") (pintype "passive"))
      (node (ref "LED7") (pin "K") (pinfunction "C_K") (pintype "passive"))
      (node (ref "LED8") (pin "K") (pinfunction "C_K") (pintype "passive"))
      (node (ref "OK1") (pin "5") (pinfunction "GND_5") (pintype "passive"))
      (node (ref "R1") (pin "1") (pinfunction "E_1") (pintype "passive"))
      (node (ref "R11") (pin "P$3") (pinfunction "A_P$3") (pintype "passive"))
      (node (ref "R12") (pin "P$3") (pinfunction "A_P$3") (pintype "passive"))
      (node (ref "R13") (pin "P$3") (pinfunction "A_P$3") (pintype "passive"))
      (node (ref "R14") (pin "P$3") (pinfunction "A_P$3") (pintype "passive"))
      (node (ref "R20") (pin "P$3") (pinfunction "A_P$3") (pintype "passive"))
      (node (ref "R21") (pin "P$3") (pinfunction "A_P$3") (pintype "passive"))
      (node (ref "R22") (pin "P$3") (pinfunction "A_P$3") (pintype "passive"))
      (node (ref "R23") (pin "P$3") (pinfunction "A_P$3") (pintype "passive"))
      (node (ref "R24") (pin "P$3") (pinfunction "A_P$3") (pintype "passive"))
      (node (ref "R25") (pin "P$3") (pinfunction "A_P$3") (pintype "passive"))
      (node (ref "R26") (pin "P$3") (pinfunction "A_P$3") (pintype "passive"))
      (node (ref "R27") (pin "P$3") (pinfunction "A_P$3") (pintype "passive"))
      (node (ref "R28") (pin "P$3") (pinfunction "A_P$3") (pintype "passive"))
      (node (ref "R29") (pin "P$3") (pinfunction "A_P$3") (pintype "passive"))
      (node (ref "R3") (pin "P$3") (pinfunction "A_P$3") (pintype "passive"))
      (node (ref "R30") (pin "P$3") (pinfunction "A_P$3") (pintype "passive"))
      (node (ref "R39") (pin "P$3") (pinfunction "A_P$3") (pintype "passive"))
      (node (ref "R4") (pin "P$3") (pinfunction "A_P$3") (pintype "passive"))
      (node (ref "R40") (pin "P$3") (pinfunction "A_P$3") (pintype "passive"))
      (node (ref "R41") (pin "P$3") (pinfunction "A_P$3") (pintype "passive"))
      (node (ref "R42") (pin "P$3") (pinfunction "A_P$3") (pintype "passive"))
      (node (ref "R43") (pin "P$3") (pinfunction "A_P$3") (pintype "passive"))
      (node (ref "R44") (pin "P$3") (pinfunction "A_P$3") (pintype "passive"))
      (node (ref "R45") (pin "P$3") (pinfunction "A_P$3") (pintype "passive"))
      (node (ref "R46") (pin "P$3") (pinfunction "A_P$3") (pintype "passive"))
      (node (ref "R5") (pin "P$3") (pinfunction "A_P$3") (pintype "passive"))
      (node (ref "R6") (pin "P$3") (pinfunction "A_P$3") (pintype "passive"))
      (node (ref "R7") (pin "P$3") (pinfunction "A_P$3") (pintype "passive"))
      (node (ref "S1") (pin "3") (pinfunction "P_3") (pintype "passive"))
      (node (ref "S1") (pin "4") (pinfunction "P1_4") (pintype "passive"))
      (node (ref "S10") (pin "3") (pinfunction "P_3") (pintype "passive"))
      (node (ref "S10") (pin "4") (pinfunction "P1_4") (pintype "passive"))
      (node (ref "S11") (pin "3") (pinfunction "P_3") (pintype "passive"))
      (node (ref "S11") (pin "4") (pinfunction "P1_4") (pintype "passive"))
      (node (ref "S12") (pin "3") (pinfunction "P_3") (pintype "passive"))
      (node (ref "S12") (pin "4") (pinfunction "P1_4") (pintype "passive"))
      (node (ref "S13") (pin "3") (pinfunction "P_3") (pintype "passive"))
      (node (ref "S13") (pin "4") (pinfunction "P1_4") (pintype "passive"))
      (node (ref "S14") (pin "3") (pinfunction "P_3") (pintype "passive"))
      (node (ref "S14") (pin "4") (pinfunction "P1_4") (pintype "passive"))
      (node (ref "S15") (pin "3") (pinfunction "P_3") (pintype "passive"))
      (node (ref "S15") (pin "4") (pinfunction "P1_4") (pintype "passive"))
      (node (ref "S16") (pin "3") (pinfunction "P_3") (pintype "passive"))
      (node (ref "S16") (pin "4") (pinfunction "P1_4") (pintype "passive"))
      (node (ref "S17") (pin "3") (pinfunction "P_3") (pintype "passive"))
      (node (ref "S17") (pin "4") (pinfunction "P1_4") (pintype "passive"))
      (node (ref "S18") (pin "3") (pinfunction "P_3") (pintype "passive"))
      (node (ref "S18") (pin "4") (pinfunction "P1_4") (pintype "passive"))
      (node (ref "S19") (pin "3") (pinfunction "P_3") (pintype "passive"))
      (node (ref "S19") (pin "4") (pinfunction "P1_4") (pintype "passive"))
      (node (ref "S2") (pin "3") (pinfunction "P_3") (pintype "passive"))
      (node (ref "S2") (pin "4") (pinfunction "P1_4") (pintype "passive"))
      (node (ref "S3") (pin "3") (pinfunction "P_3") (pintype "passive"))
      (node (ref "S3") (pin "4") (pinfunction "P1_4") (pintype "passive"))
      (node (ref "S4") (pin "3") (pinfunction "P_3") (pintype "passive"))
      (node (ref "S4") (pin "4") (pinfunction "P1_4") (pintype "passive"))
      (node (ref "S5") (pin "3") (pinfunction "P_3") (pintype "passive"))
      (node (ref "S5") (pin "4") (pinfunction "P1_4") (pintype "passive"))
      (node (ref "S6") (pin "3") (pinfunction "P_3") (pintype "passive"))
      (node (ref "S6") (pin "4") (pinfunction "P1_4") (pintype "passive"))
      (node (ref "S7") (pin "3") (pinfunction "P_3") (pintype "passive"))
      (node (ref "S7") (pin "4") (pinfunction "P1_4") (pintype "passive"))
      (node (ref "S8") (pin "3") (pinfunction "P_3") (pintype "passive"))
      (node (ref "S8") (pin "4") (pinfunction "P1_4") (pintype "passive"))
      (node (ref "S9") (pin "3") (pinfunction "P_3") (pintype "passive"))
      (node (ref "S9") (pin "4") (pinfunction "P1_4") (pintype "passive"))
      (node (ref "SW1") (pin "C") (pinfunction "C_C") (pintype "passive"))
      (node (ref "SW1") (pin "D") (pinfunction "1_D") (pintype "passive"))
      (node (ref "U1") (pin "6") (pinfunction "6_6") (pintype "passive"))
      (node (ref "X2") (pin "2") (pinfunction "2_2") (pintype "passive"))
    )
    (net (code "27") (name "INPUT_CHAIN_1") (class "Default")
      (node (ref "IC3") (pin "9") (pinfunction "QH_9") (pintype "output"))
      (node (ref "IC9") (pin "10") (pinfunction "SER_10") (pintype "input"))
    )
    (net (code "28") (name "INPUT_CHAIN_2") (class "Default")
      (node (ref "IC2") (pin "10") (pinfunction "SER_10") (pintype "input"))
      (node (ref "IC9") (pin "9") (pinfunction "QH_9") (pintype "output"))
    )
    (net (code "29") (name "IO_CHAIN") (class "Default")
      (node (ref "IC8") (pin "9") (pinfunction "QH*_9") (pintype "tri_state"))
      (node (ref "J3") (pin "1") (pinfunction "1_1") (pintype "passive"))
    )
    (net (code "30") (name "IO_ENABLE") (class "Default")
      (node (ref "IC10") (pin "16") (pinfunction "(INT0)PD2_16") (pintype "bidirectional"))
      (node (ref "IC2") (pin "1") (pinfunction "SH/~{LD}_1") (pintype "input"))
      (node (ref "IC3") (pin "1") (pinfunction "SH/~{LD}_1") (pintype "input"))
      (node (ref "IC8") (pin "12") (pinfunction "RCK_12") (pintype "input"))
      (node (ref "IC9") (pin "1") (pinfunction "SH/~{LD}_1") (pintype "input"))
      (node (ref "J3") (pin "3") (pinfunction "3_3") (pintype "passive"))
    )
    (net (code "31") (name "IO_MISO") (class "Default")
      (node (ref "IC10") (pin "7") (pinfunction "(MISO)PB6_7") (pintype "bidirectional"))
      (node (ref "IC2") (pin "9") (pinfunction "QH_9") (pintype "output"))
      (node (ref "U1") (pin "1") (pinfunction "1_1") (pintype "passive"))
    )
    (net (code "32") (name "IO_MOSI") (class "Default")
      (node (ref "IC10") (pin "6") (pinfunction "(MOSI)PB5_6") (pintype "bidirectional"))
      (node (ref "IC8") (pin "14") (pinfunction "SER_14") (pintype "input"))
      (node (ref "U1") (pin "4") (pinfunction "4_4") (pintype "passive"))
    )
    (net (code "33") (name "IO_SCK") (class "Default")
      (node (ref "IC10") (pin "8") (pinfunction "(SCK)PB7_8") (pintype "bidirectional"))
      (node (ref "IC2") (pin "2") (pinfunction "CLK_2") (pintype "input"))
      (node (ref "IC3") (pin "2") (pinfunction "CLK_2") (pintype "input"))
      (node (ref "IC8") (pin "11") (pinfunction "SCK_11") (pintype "input"))
      (node (ref "IC9") (pin "2") (pinfunction "CLK_2") (pintype "input"))
      (node (ref "J3") (pin "2") (pinfunction "2_2") (pintype "passive"))
      (node (ref "U1") (pin "3") (pinfunction "3_3") (pintype "passive"))
    )
    (net (code "34") (name "LCD_DATA1") (class "Default")
      (node (ref "IC10") (pin "26") (pinfunction "(TDO)PC4_26") (pintype "bidirectional"))
      (node (ref "LCD") (pin "11") (pinfunction "DB4_11") (pintype "bidirectional"))
    )
    (net (code "35") (name "LCD_DATA2") (class "Default")
      (node (ref "IC10") (pin "27") (pinfunction "(TDI)PC5_27") (pintype "bidirectional"))
      (node (ref "LCD") (pin "12") (pinfunction "DB5_12") (pintype "bidirectional"))
    )
    (net (code "36") (name "LCD_DATA3") (class "Default")
      (node (ref "IC10") (pin "28") (pinfunction "(TOSC1)PC6_28") (pintype "bidirectional"))
      (node (ref "LCD") (pin "13") (pinfunction "DB6_13") (pintype "bidirectional"))
    )
    (net (code "37") (name "LCD_DATA4") (class "Default")
      (node (ref "IC10") (pin "29") (pinfunction "(TOSC2)PC7_29") (pintype "bidirectional"))
      (node (ref "LCD") (pin "14") (pinfunction "DB7_14") (pintype "bidirectional"))
    )
    (net (code "38") (name "LCD_EN") (class "Default")
      (node (ref "IC10") (pin "25") (pinfunction "(TMS)PC3_25") (pintype "bidirectional"))
      (node (ref "LCD") (pin "6") (pinfunction "E_6") (pintype "input"))
    )
    (net (code "39") (name "LCD_RS") (class "Default")
      (node (ref "IC10") (pin "24") (pinfunction "(TCK)PC2_24") (pintype "bidirectional"))
      (node (ref "LCD") (pin "4") (pinfunction "RS_4") (pintype "input"))
    )
    (net (code "40") (name "LFO1_ATTACK") (class "Default")
      (node (ref "IC6") (pin "12") (pinfunction "X3_12") (pintype "bidirectional"))
      (node (ref "R14") (pin "P$2") (pinfunction "S_P$2") (pintype "passive"))
    )
    (net (code "41") (name "LFO1_RATE") (class "Default")
      (node (ref "IC6") (pin "15") (pinfunction "X2_15") (pintype "bidirectional"))
      (node (ref "R13") (pin "P$2") (pinfunction "S_P$2") (pintype "passive"))
    )
    (net (code "42") (name "LFO2_ATTACK") (class "Default")
      (node (ref "IC6") (pin "13") (pinfunction "X0_13") (pintype "bidirectional"))
      (node (ref "R7") (pin "P$2") (pinfunction "S_P$2") (pintype "passive"))
    )
    (net (code "43") (name "LFO2_RATE") (class "Default")
      (node (ref "IC6") (pin "14") (pinfunction "X1_14") (pintype "bidirectional"))
      (node (ref "R6") (pin "P$2") (pinfunction "S_P$2") (pintype "passive"))
    )
    (net (code "44") (name "MIDI_RX") (class "Default")
      (node (ref "IC10") (pin "14") (pinfunction "(RXD)PD0_14") (pintype "bidirectional"))
      (node (ref "OK1") (pin "6") (pinfunction "VO_6") (pintype "passive"))
      (node (ref "R18") (pin "2") (pinfunction "2_2") (pintype "passive"))
    )
    (net (code "45") (name "MIDI_TX") (class "Default")
      (node (ref "IC10") (pin "15") (pinfunction "(TXD)PD1_15") (pintype "bidirectional"))
      (node (ref "R15") (pin "2") (pinfunction "2_2") (pintype "passive"))
    )
    (net (code "46") (name "MIX_BALANCE") (class "Default")
      (node (ref "IC4") (pin "2") (pinfunction "X6_2") (pintype "bidirectional"))
      (node (ref "R20") (pin "P$2") (pinfunction "S_P$2") (pintype "passive"))
    )
    (net (code "47") (name "MIX_NOISE") (class "Default")
      (node (ref "IC4") (pin "4") (pinfunction "X7_4") (pintype "bidirectional"))
      (node (ref "R21") (pin "P$2") (pinfunction "S_P$2") (pintype "passive"))
    )
    (net (code "48") (name "MIX_SUB") (class "Default")
      (node (ref "IC4") (pin "5") (pinfunction "X5_5") (pintype "bidirectional"))
      (node (ref "R22") (pin "P$2") (pinfunction "S_P$2") (pintype "passive"))
    )
    (net (code "49") (name "MUX_ADDR0") (class "Default")
      (node (ref "IC10") (pin "39") (pinfunction "(ADC1)PA1_39") (pintype "bidirectional"))
      (node (ref "IC4") (pin "11") (pinfunction "A_11") (pintype "input"))
      (node (ref "IC5") (pin "11") (pinfunction "A_11") (pintype "input"))
      (node (ref "IC6") (pin "11") (pinfunction "A_11") (pintype "input"))
      (node (ref "IC7") (pin "11") (pinfunction "A_11") (pintype "input"))
    )
    (net (code "50") (name "MUX_ADDR1") (class "Default")
      (node (ref "IC10") (pin "38") (pinfunction "(ADC2)PA2_38") (pintype "bidirectional"))
      (node (ref "IC4") (pin "10") (pinfunction "B_10") (pintype "input"))
      (node (ref "IC5") (pin "10") (pinfunction "B_10") (pintype "input"))
      (node (ref "IC6") (pin "10") (pinfunction "B_10") (pintype "input"))
      (node (ref "IC7") (pin "10") (pinfunction "B_10") (pintype "input"))
    )
    (net (code "51") (name "MUX_ADDR2") (class "Default")
      (node (ref "IC10") (pin "37") (pinfunction "(ADC3)PA3_37") (pintype "bidirectional"))
      (node (ref "IC4") (pin "9") (pinfunction "C_9") (pintype "input"))
      (node (ref "IC5") (pin "9") (pinfunction "C_9") (pintype "input"))
      (node (ref "IC6") (pin "9") (pinfunction "C_9") (pintype "input"))
      (node (ref "IC7") (pin "9") (pinfunction "C_9") (pintype "input"))
    )
    (net (code "52") (name "MUX_EN0") (class "Default")
      (node (ref "IC10") (pin "36") (pinfunction "(ADC4)PA4_36") (pintype "bidirectional"))
      (node (ref "IC6") (pin "6") (pinfunction "INH_6") (pintype "input"))
    )
    (net (code "53") (name "MUX_EN1") (class "Default")
      (node (ref "IC10") (pin "35") (pinfunction "(ADC5)PA5_35") (pintype "bidirectional"))
      (node (ref "IC7") (pin "6") (pinfunction "INH_6") (pintype "input"))
    )
    (net (code "54") (name "MUX_EN2") (class "Default")
      (node (ref "IC10") (pin "34") (pinfunction "(ADC6)PA6_34") (pintype "bidirectional"))
      (node (ref "IC4") (pin "6") (pinfunction "INH_6") (pintype "input"))
    )
    (net (code "55") (name "MUX_EN3") (class "Default")
      (node (ref "IC10") (pin "33") (pinfunction "(ADC7)PA7_33") (pintype "bidirectional"))
      (node (ref "IC5") (pin "6") (pinfunction "INH_6") (pintype "input"))
    )
    (net (code "56") (name "Net-(IC2A-A)") (class "Default")
      (node (ref "IC2") (pin "11") (pinfunction "A_11") (pintype "input"))
      (node (ref "RN1") (pin "5") (pinfunction "5_5") (pintype "passive"))
      (node (ref "S2") (pin "1") (pinfunction "S_1") (pintype "passive"))
      (node (ref "S2") (pin "2") (pinfunction "S1_2") (pintype "passive"))
    )
    (net (code "57") (name "Net-(IC2A-B)") (class "Default")
      (node (ref "IC2") (pin "12") (pinfunction "B_12") (pintype "input"))
      (node (ref "RN1") (pin "4") (pinfunction "4_4") (pintype "passive"))
      (node (ref "S1") (pin "1") (pinfunction "S_1") (pintype "passive"))
      (node (ref "S1") (pin "2") (pinfunction "S1_2") (pintype "passive"))
    )
    (net (code "58") (name "Net-(IC2A-C)") (class "Default")
      (node (ref "IC2") (pin "13") (pinfunction "C_13") (pintype "input"))
      (node (ref "RN1") (pin "3") (pinfunction "3_3") (pintype "passive"))
      (node (ref "S6") (pin "1") (pinfunction "S_1") (pintype "passive"))
      (node (ref "S6") (pin "2") (pinfunction "S1_2") (pintype "passive"))
    )
    (net (code "59") (name "Net-(IC2A-D)") (class "Default")
      (node (ref "IC2") (pin "14") (pinfunction "D_14") (pintype "input"))
      (node (ref "RN1") (pin "2") (pinfunction "2_2") (pintype "passive"))
      (node (ref "S5") (pin "1") (pinfunction "S_1") (pintype "passive"))
      (node (ref "S5") (pin "2") (pinfunction "S1_2") (pintype "passive"))
    )
    (net (code "60") (name "Net-(IC2A-E)") (class "Default")
      (node (ref "IC2") (pin "3") (pinfunction "E_3") (pintype "input"))
      (node (ref "RN1") (pin "6") (pinfunction "6_6") (pintype "passive"))
      (node (ref "S13") (pin "1") (pinfunction "S_1") (pintype "passive"))
      (node (ref "S13") (pin "2") (pinfunction "S1_2") (pintype "passive"))
    )
    (net (code "61") (name "Net-(IC2A-F)") (class "Default")
      (node (ref "IC2") (pin "4") (pinfunction "F_4") (pintype "input"))
      (node (ref "RN1") (pin "7") (pinfunction "7_7") (pintype "passive"))
      (node (ref "S12") (pin "1") (pinfunction "S_1") (pintype "passive"))
      (node (ref "S12") (pin "2") (pinfunction "S1_2") (pintype "passive"))
    )
    (net (code "62") (name "Net-(IC2A-G)") (class "Default")
      (node (ref "IC2") (pin "5") (pinfunction "G_5") (pintype "input"))
      (node (ref "RN1") (pin "8") (pinfunction "8_8") (pintype "passive"))
      (node (ref "S7") (pin "1") (pinfunction "S_1") (pintype "passive"))
      (node (ref "S7") (pin "2") (pinfunction "S1_2") (pintype "passive"))
    )
    (net (code "63") (name "Net-(IC2A-H)") (class "Default")
      (node (ref "IC2") (pin "6") (pinfunction "H_6") (pintype "input"))
      (node (ref "RN1") (pin "9") (pinfunction "9_9") (pintype "passive"))
      (node (ref "S8") (pin "1") (pinfunction "S_1") (pintype "passive"))
      (node (ref "S8") (pin "2") (pinfunction "S1_2") (pintype "passive"))
    )
    (net (code "64") (name "Net-(IC3A-A)") (class "Default")
      (node (ref "IC3") (pin "11") (pinfunction "A_11") (pintype "input"))
      (node (ref "RN2") (pin "6") (pinfunction "6_6") (pintype "passive"))
      (node (ref "S11") (pin "1") (pinfunction "S_1") (pintype "passive"))
      (node (ref "S11") (pin "2") (pinfunction "S1_2") (pintype "passive"))
    )
    (net (code "65") (name "Net-(IC3A-B)") (class "Default")
      (node (ref "IC3") (pin "12") (pinfunction "B_12") (pintype "input"))
      (node (ref "RN2") (pin "5") (pinfunction "5_5") (pintype "passive"))
      (node (ref "S10") (pin "1") (pinfunction "S_1") (pintype "passive"))
      (node (ref "S10") (pin "2") (pinfunction "S1_2") (pintype "passive"))
    )
    (net (code "66") (name "Net-(IC3A-C)") (class "Default")
      (node (ref "IC3") (pin "13") (pinfunction "C_13") (pintype "input"))
      (node (ref "RN2") (pin "4") (pinfunction "4_4") (pintype "passive"))
      (node (ref "S9") (pin "1") (pinfunction "S_1") (pintype "passive"))
      (node (ref "S9") (pin "2") (pinfunction "S1_2") (pintype "passive"))
    )
    (net (code "67") (name "Net-(IC3A-D)") (class "Default")
      (node (ref "IC3") (pin "14") (pinfunction "D_14") (pintype "input"))
      (node (ref "RN2") (pin "3") (pinfunction "3_3") (pintype "passive"))
      (node (ref "S4") (pin "1") (pinfunction "S_1") (pintype "passive"))
      (node (ref "S4") (pin "2") (pinfunction "S1_2") (pintype "passive"))
    )
    (net (code "68") (name "Net-(IC3A-E)") (class "Default")
      (node (ref "IC3") (pin "3") (pinfunction "E_3") (pintype "input"))
      (node (ref "RN2") (pin "2") (pinfunction "2_2") (pintype "passive"))
      (node (ref "S3") (pin "1") (pinfunction "S_1") (pintype "passive"))
      (node (ref "S3") (pin "2") (pinfunction "S1_2") (pintype "passive"))
    )
    (net (code "69") (name "Net-(IC8A-QA)") (class "Default")
      (node (ref "IC8") (pin "15") (pinfunction "QA_15") (pintype "tri_state"))
      (node (ref "R31") (pin "1") (pinfunction "1_1") (pintype "passive"))
    )
    (net (code "70") (name "Net-(IC8A-QB)") (class "Default")
      (node (ref "IC8") (pin "1") (pinfunction "QB_1") (pintype "tri_state"))
      (node (ref "R33") (pin "1") (pinfunction "1_1") (pintype "passive"))
    )
    (net (code "71") (name "Net-(IC8A-QC)") (class "Default")
      (node (ref "IC8") (pin "2") (pinfunction "QC_2") (pintype "tri_state"))
      (node (ref "R34") (pin "1") (pinfunction "1_1") (pintype "passive"))
    )
    (net (code "72") (name "Net-(IC8A-QD)") (class "Default")
      (node (ref "IC8") (pin "3") (pinfunction "QD_3") (pintype "tri_state"))
      (node (ref "R32") (pin "1") (pinfunction "1_1") (pintype "passive"))
    )
    (net (code "73") (name "Net-(IC8A-QE)") (class "Default")
      (node (ref "IC8") (pin "4") (pinfunction "QE_4") (pintype "tri_state"))
      (node (ref "R35") (pin "1") (pinfunction "1_1") (pintype "passive"))
    )
    (net (code "74") (name "Net-(IC8A-QF)") (class "Default")
      (node (ref "IC8") (pin "5") (pinfunction "QF_5") (pintype "tri_state"))
      (node (ref "R36") (pin "1") (pinfunction "1_1") (pintype "passive"))
    )
    (net (code "75") (name "Net-(IC8A-QG)") (class "Default")
      (node (ref "IC8") (pin "6") (pinfunction "QG_6") (pintype "tri_state"))
      (node (ref "R37") (pin "1") (pinfunction "1_1") (pintype "passive"))
    )
    (net (code "76") (name "Net-(IC8A-QH)") (class "Default")
      (node (ref "IC8") (pin "7") (pinfunction "QH_7") (pintype "tri_state"))
      (node (ref "R38") (pin "1") (pinfunction "1_1") (pintype "passive"))
    )
    (net (code "77") (name "Net-(IC9A-A)") (class "Default")
      (node (ref "IC9") (pin "11") (pinfunction "A_11") (pintype "input"))
      (node (ref "RN3") (pin "7") (pinfunction "7_7") (pintype "passive"))
      (node (ref "S19") (pin "1") (pinfunction "S_1") (pintype "passive"))
      (node (ref "S19") (pin "2") (pinfunction "S1_2") (pintype "passive"))
    )
    (net (code "78") (name "Net-(IC9A-B)") (class "Default")
      (node (ref "IC9") (pin "12") (pinfunction "B_12") (pintype "input"))
      (node (ref "RN3") (pin "6") (pinfunction "6_6") (pintype "passive"))
      (node (ref "S18") (pin "1") (pinfunction "S_1") (pintype "passive"))
      (node (ref "S18") (pin "2") (pinfunction "S1_2") (pintype "passive"))
    )
    (net (code "79") (name "Net-(IC9A-C)") (class "Default")
      (node (ref "IC9") (pin "13") (pinfunction "C_13") (pintype "input"))
      (node (ref "RN3") (pin "5") (pinfunction "5_5") (pintype "passive"))
      (node (ref "S17") (pin "1") (pinfunction "S_1") (pintype "passive"))
      (node (ref "S17") (pin "2") (pinfunction "S1_2") (pintype "passive"))
    )
    (net (code "80") (name "Net-(IC9A-D)") (class "Default")
      (node (ref "IC9") (pin "14") (pinfunction "D_14") (pintype "input"))
      (node (ref "RN3") (pin "4") (pinfunction "4_4") (pintype "passive"))
      (node (ref "S16") (pin "1") (pinfunction "S_1") (pintype "passive"))
      (node (ref "S16") (pin "2") (pinfunction "S1_2") (pintype "passive"))
    )
    (net (code "81") (name "Net-(IC9A-E)") (class "Default")
      (node (ref "IC9") (pin "3") (pinfunction "E_3") (pintype "input"))
      (node (ref "RN3") (pin "3") (pinfunction "3_3") (pintype "passive"))
      (node (ref "S15") (pin "1") (pinfunction "S_1") (pintype "passive"))
      (node (ref "S15") (pin "2") (pinfunction "S1_2") (pintype "passive"))
    )
    (net (code "82") (name "Net-(IC9A-F)") (class "Default")
      (node (ref "IC9") (pin "4") (pinfunction "F_4") (pintype "input"))
      (node (ref "RN3") (pin "2") (pinfunction "2_2") (pintype "passive"))
      (node (ref "S14") (pin "1") (pinfunction "S_1") (pintype "passive"))
      (node (ref "S14") (pin "2") (pinfunction "S1_2") (pintype "passive"))
    )
    (net (code "83") (name "Net-(IC10-AREF)") (class "Default")
      (node (ref "C16") (pin "1") (pinfunction "1_1") (pintype "passive"))
      (node (ref "IC10") (pin "32") (pinfunction "AREF_32") (pintype "passive"))
    )
    (net (code "84") (name "Net-(IC10-XTAL1)") (class "Default")
      (node (ref "C11") (pin "2") (pinfunction "2_2") (pintype "passive"))
      (node (ref "IC10") (pin "13") (pinfunction "XTAL1_13") (pintype "bidirectional"))
      (node (ref "Q1") (pin "1") (pinfunction "1_1") (pintype "passive"))
    )
    (net (code "85") (name "Net-(IC10-XTAL2)") (class "Default")
      (node (ref "C12") (pin "2") (pinfunction "2_2") (pintype "passive"))
      (node (ref "IC10") (pin "12") (pinfunction "XTAL2_12") (pintype "bidirectional"))
      (node (ref "Q1") (pin "2") (pinfunction "2_2") (pintype "passive"))
    )
    (net (code "86") (name "Net-(LCD-A)") (class "Default")
      (node (ref "LCD") (pin "15") (pinfunction "A_15") (pintype "power_in"))
      (node (ref "R2") (pin "2") (pinfunction "2_2") (pintype "passive"))
    )
    (net (code "87") (name "Net-(LCD-VO)") (class "Default")
      (node (ref "LCD") (pin "3") (pinfunction "VO_3") (pintype "bidirectional"))
      (node (ref "R1") (pin "2") (pinfunction "S_2") (pintype "passive"))
    )
    (net (code "88") (name "Net-(LED1-PadA)") (class "Default")
      (node (ref "LED1") (pin "A") (pinfunction "A_A") (pintype "passive"))
      (node (ref "R31") (pin "2") (pinfunction "2_2") (pintype "passive"))
    )
    (net (code "89") (name "Net-(LED2-PadA)") (class "Default")
      (node (ref "LED2") (pin "A") (pinfunction "A_A") (pintype "passive"))
      (node (ref "R33") (pin "2") (pinfunction "2_2") (pintype "passive"))
    )
    (net (code "90") (name "Net-(LED3-PadA)") (class "Default")
      (node (ref "LED3") (pin "A") (pinfunction "A_A") (pintype "passive"))
      (node (ref "R34") (pin "2") (pinfunction "2_2") (pintype "passive"))
    )
    (net (code "91") (name "Net-(LED4-PadA)") (class "Default")
      (node (ref "LED4") (pin "A") (pinfunction "A_A") (pintype "passive"))
      (node (ref "R32") (pin "2") (pinfunction "2_2") (pintype "passive"))
    )
    (net (code "92") (name "Net-(LED5-PadA)") (class "Default")
      (node (ref "LED5") (pin "A") (pinfunction "A_A") (pintype "passive"))
      (node (ref "R35") (pin "2") (pinfunction "2_2") (pintype "passive"))
    )
    (net (code "93") (name "Net-(LED6-PadA)") (class "Default")
      (node (ref "LED6") (pin "A") (pinfunction "A_A") (pintype "passive"))
      (node (ref "R36") (pin "2") (pinfunction "2_2") (pintype "passive"))
    )
    (net (code "94") (name "Net-(LED7-PadA)") (class "Default")
      (node (ref "LED7") (pin "A") (pinfunction "A_A") (pintype "passive"))
      (node (ref "R37") (pin "2") (pinfunction "2_2") (pintype "passive"))
    )
    (net (code "95") (name "Net-(LED8-PadA)") (class "Default")
      (node (ref "LED8") (pin "A") (pinfunction "A_A") (pintype "passive"))
      (node (ref "R38") (pin "2") (pinfunction "2_2") (pintype "passive"))
    )
    (net (code "96") (name "Net-(OK1-A)") (class "Default")
      (node (ref "D1") (pin "C") (pinfunction "C_C") (pintype "passive"))
      (node (ref "OK1") (pin "2") (pinfunction "A_2") (pintype "passive"))
      (node (ref "R16") (pin "2") (pinfunction "2_2") (pintype "passive"))
    )
    (net (code "97") (name "Net-(OK1-C)") (class "Default")
      (node (ref "D1") (pin "A") (pinfunction "A_A") (pintype "passive"))
      (node (ref "OK1") (pin "3") (pinfunction "C_3") (pintype "passive"))
      (node (ref "X1") (pin "5") (pinfunction "5_5") (pintype "passive"))
    )
    (net (code "98") (name "Net-(R8-A)") (class "Default")
      (node (ref "JP2") (pin "3") (pinfunction "3_3") (pintype "passive"))
      (node (ref "R8") (pin "P$3") (pinfunction "A_P$3") (pintype "passive"))
    )
    (net (code "99") (name "Net-(R8-E)") (class "Default")
      (node (ref "JP2") (pin "1") (pinfunction "1_1") (pintype "passive"))
      (node (ref "R8") (pin "P$1") (pinfunction "E_P$1") (pintype "passive"))
    )
    (net (code "100") (name "Net-(R8-S)") (class "Default")
      (node (ref "JP2") (pin "2") (pinfunction "2_2") (pintype "passive"))
      (node (ref "R8") (pin "P$2") (pinfunction "S_P$2") (pintype "passive"))
    )
    (net (code "101") (name "Net-(R15-Pad1)") (class "Default")
      (node (ref "R15") (pin "1") (pinfunction "1_1") (pintype "passive"))
      (node (ref "X2") (pin "5") (pinfunction "5_5") (pintype "passive"))
    )
    (net (code "102") (name "Net-(R16-Pad1)") (class "Default")
      (node (ref "R16") (pin "1") (pinfunction "1_1") (pintype "passive"))
      (node (ref "X1") (pin "4") (pinfunction "4_4") (pintype "passive"))
    )
    (net (code "103") (name "Net-(R17-Pad1)") (class "Default")
      (node (ref "R17") (pin "1") (pinfunction "1_1") (pintype "passive"))
      (node (ref "X2") (pin "4") (pinfunction "4_4") (pintype "passive"))
    )
    (net (code "104") (name "OSC") (class "Default")
      (node (ref "IC10") (pin "18") (pinfunction "(OC1B)PD4_18") (pintype "bidirectional"))
      (node (ref "J1") (pin "1") (pinfunction "1_1") (pintype "passive"))
    )
    (net (code "105") (name "OSC1_PARAMETER") (class "Default")
      (node (ref "IC4") (pin "14") (pinfunction "X1_14") (pintype "bidirectional"))
      (node (ref "R11") (pin "P$2") (pinfunction "S_P$2") (pintype "passive"))
    )
    (net (code "106") (name "OSC1_RANGE") (class "Default")
      (node (ref "IC4") (pin "12") (pinfunction "X3_12") (pintype "bidirectional"))
      (node (ref "R12") (pin "P$2") (pinfunction "S_P$2") (pintype "passive"))
    )
    (net (code "107") (name "OSC2_DETUNE") (class "Default")
      (node (ref "IC4") (pin "1") (pinfunction "X4_1") (pintype "bidirectional"))
      (node (ref "R5") (pin "P$2") (pinfunction "S_P$2") (pintype "passive"))
    )
    (net (code "108") (name "OSC2_PARAMETER") (class "Default")
      (node (ref "IC4") (pin "15") (pinfunction "X2_15") (pintype "bidirectional"))
      (node (ref "R3") (pin "P$2") (pinfunction "S_P$2") (pintype "passive"))
    )
    (net (code "109") (name "OSC2_RANGE") (class "Default")
      (node (ref "IC4") (pin "13") (pinfunction "X0_13") (pintype "bidirectional"))
      (node (ref "R4") (pin "P$2") (pinfunction "S_P$2") (pintype "passive"))
    )
    (net (code "110") (name "RESET") (class "Default")
      (node (ref "C10") (pin "1") (pinfunction "1_1") (pintype "passive"))
      (node (ref "IC10") (pin "9") (pinfunction "RESET_9") (pintype "input"))
      (node (ref "R19") (pin "1") (pinfunction "1_1") (pintype "passive"))
      (node (ref "U1") (pin "5") (pinfunction "5_5") (pintype "passive"))
    )
    (net (code "111") (name "RESONANCE") (class "Default")
      (node (ref "IC5") (pin "5") (pinfunction "X5_5") (pintype "bidirectional"))
      (node (ref "R40") (pin "P$2") (pinfunction "S_P$2") (pintype "passive"))
    )
    (net (code "112") (name "SCL") (class "Default")
      (node (ref "IC1") (pin "6") (pinfunction "SCL_6") (pintype "bidirectional"))
      (node (ref "IC10") (pin "22") (pinfunction "(SCL)PC0_22") (pintype "bidirectional"))
      (node (ref "R10") (pin "2") (pinfunction "2_2") (pintype "passive"))
    )
    (net (code "113") (name "SDA") (class "Default")
      (node (ref "IC1") (pin "5") (pinfunction "SDA_5") (pintype "bidirectional"))
      (node (ref "IC10") (pin "23") (pinfunction "(SDA)PC1_23") (pintype "bidirectional"))
      (node (ref "R9") (pin "2") (pinfunction "2_2") (pintype "passive"))
    )
    (net (code "114") (name "VCC") (class "Default")
      (node (ref "C1") (pin "1") (pinfunction "1_1") (pintype "passive"))
      (node (ref "C13") (pin "1") (pinfunction "1_1") (pintype "passive"))
      (node (ref "C14") (pin "1") (pinfunction "1_1") (pintype "passive"))
      (node (ref "C15") (pin "1") (pinfunction "1_1") (pintype "passive"))
      (node (ref "C17") (pin "1") (pinfunction "1_1") (pintype "passive"))
      (node (ref "C2") (pin "1") (pinfunction "1_1") (pintype "passive"))
      (node (ref "C3") (pin "1") (pinfunction "1_1") (pintype "passive"))
      (node (ref "C4") (pin "+") (pinfunction "+_+") (pintype "passive"))
      (node (ref "C5") (pin "1") (pinfunction "1_1") (pintype "passive"))
      (node (ref "C6") (pin "1") (pinfunction "1_1") (pintype "passive"))
      (node (ref "C7") (pin "1") (pinfunction "1_1") (pintype "passive"))
      (node (ref "C8") (pin "1") (pinfunction "1_1") (pintype "passive"))
      (node (ref "C9") (pin "1") (pinfunction "1_1") (pintype "passive"))
      (node (ref "IC1") (pin "8") (pinfunction "VCC_8") (pintype "power_in"))
      (node (ref "IC10") (pin "10") (pinfunction "VCC_10") (pintype "power_in"))
      (node (ref "IC10") (pin "30") (pinfunction "AVCC_30") (pintype "power_in"))
      (node (ref "IC2") (pin "16") (pinfunction "VCC_16") (pintype "power_in"))
      (node (ref "IC3") (pin "16") (pinfunction "VCC_16") (pintype "power_in"))
      (node (ref "IC4") (pin "16") (pinfunction "VCC_16") (pintype "power_in"))
      (node (ref "IC5") (pin "16") (pinfunction "VCC_16") (pintype "power_in"))
      (node (ref "IC6") (pin "16") (pinfunction "VCC_16") (pintype "power_in"))
      (node (ref "IC7") (pin "16") (pinfunction "VCC_16") (pintype "power_in"))
      (node (ref "IC8") (pin "10") (pinfunction "SCL_10") (pintype "input"))
      (node (ref "IC8") (pin "16") (pinfunction "VCC_16") (pintype "power_in"))
      (node (ref "IC9") (pin "16") (pinfunction "VCC_16") (pintype "power_in"))
      (node (ref "J2") (pin "2") (pinfunction "2_2") (pintype "passive"))
      (node (ref "J4") (pin "2") (pinfunction "2_2") (pintype "passive"))
      (node (ref "JP1") (pin "3") (pinfunction "3_3") (pintype "passive"))
      (node (ref "LCD") (pin "2") (pinfunction "VDD_2") (pintype "power_in"))
      (node (ref "OK1") (pin "8") (pinfunction "VCC_8") (pintype "passive"))
      (node (ref "R1") (pin "3") (pinfunction "A_3") (pintype "passive"))
      (node (ref "R10") (pin "1") (pinfunction "1_1") (pintype "passive"))
      (node (ref "R11") (pin "P$1") (pinfunction "E_P$1") (pintype "passive"))
      (node (ref "R12") (pin "P$1") (pinfunction "E_P$1") (pintype "passive"))
      (node (ref "R13") (pin "P$1") (pinfunction "E_P$1") (pintype "passive"))
      (node (ref "R14") (pin "P$1") (pinfunction "E_P$1") (pintype "passive"))
      (node (ref "R17") (pin "2") (pinfunction "2_2") (pintype "passive"))
      (node (ref "R18") (pin "1") (pinfunction "1_1") (pintype "passive"))
      (node (ref "R19") (pin "2") (pinfunction "2_2") (pintype "passive"))
      (node (ref "R2") (pin "1") (pinfunction "1_1") (pintype "passive"))
      (node (ref "R20") (pin "P$1") (pinfunction "E_P$1") (pintype "passive"))
      (node (ref "R21") (pin "P$1") (pinfunction "E_P$1") (pintype "passive"))
      (node (ref "R22") (pin "P$1") (pinfunction "E_P$1") (pintype "passive"))
      (node (ref "R23") (pin "P$1") (pinfunction "E_P$1") (pintype "passive"))
      (node (ref "R24") (pin "P$1") (pinfunction "E_P$1") (pintype "passive"))
      (node (ref "R25") (pin "P$1") (pinfunction "E_P$1") (pintype "passive"))
      (node (ref "R26") (pin "P$1") (pinfunction "E_P$1") (pintype "passive"))
      (node (ref "R27") (pin "P$1") (pinfunction "E_P$1") (pintype "passive"))
      (node (ref "R28") (pin "P$1") (pinfunction "E_P$1") (pintype "passive"))
      (node (ref "R29") (pin "P$1") (pinfunction "E_P$1") (pintype "passive"))
      (node (ref "R3") (pin "P$1") (pinfunction "E_P$1") (pintype "passive"))
      (node (ref "R30") (pin "P$1") (pinfunction "E_P$1") (pintype "passive"))
      (node (ref "R39") (pin "P$1") (pinfunction "E_P$1") (pintype "passive"))
      (node (ref "R4") (pin "P$1") (pinfunction "E_P$1") (pintype "passive"))
      (node (ref "R40") (pin "P$1") (pinfunction "E_P$1") (pintype "passive"))
      (node (ref "R41") (pin "P$1") (pinfunction "E_P$1") (pintype "passive"))
      (node (ref "R42") (pin "P$1") (pinfunction "E_P$1") (pintype "passive"))
      (node (ref "R43") (pin "P$1") (pinfunction "E_P$1") (pintype "passive"))
      (node (ref "R44") (pin "P$1") (pinfunction "E_P$1") (pintype "passive"))
      (node (ref "R45") (pin "P$1") (pinfunction "E_P$1") (pintype "passive"))
      (node (ref "R46") (pin "P$1") (pinfunction "E_P$1") (pintype "passive"))
      (node (ref "R5") (pin "P$1") (pinfunction "E_P$1") (pintype "passive"))
      (node (ref "R6") (pin "P$1") (pinfunction "E_P$1") (pintype "passive"))
      (node (ref "R7") (pin "P$1") (pinfunction "E_P$1") (pintype "passive"))
      (node (ref "R9") (pin "1") (pinfunction "1_1") (pintype "passive"))
      (node (ref "RN1") (pin "1") (pinfunction "1_1") (pintype "passive"))
      (node (ref "RN2") (pin "1") (pinfunction "1_1") (pintype "passive"))
      (node (ref "RN3") (pin "1") (pinfunction "1_1") (pintype "passive"))
      (node (ref "U1") (pin "2") (pinfunction "2_2") (pintype "passive"))
    )
    (net (code "115") (name "VOLUME") (class "Default")
      (node (ref "IC7") (pin "15") (pinfunction "X2_15") (pintype "bidirectional"))
      (node (ref "JP1") (pin "2") (pinfunction "2_2") (pintype "passive"))
    )
    (net (code "116") (name "unconnected-(IC2A-~{QH}-Pad7)") (class "Default")
      (node (ref "IC2") (pin "7") (pinfunction "~{QH}_7") (pintype "output"))
    )
    (net (code "117") (name "unconnected-(IC3A-~{QH}-Pad7)") (class "Default")
      (node (ref "IC3") (pin "7") (pinfunction "~{QH}_7") (pintype "output"))
    )
    (net (code "118") (name "unconnected-(IC9A-~{QH}-Pad7)") (class "Default")
      (node (ref "IC9") (pin "7") (pinfunction "~{QH}_7") (pintype "output"))
    )
    (net (code "119") (name "unconnected-(LCD-DB0-Pad7)") (class "Default")
      (node (ref "LCD") (pin "7") (pinfunction "DB0_7") (pintype "bidirectional"))
    )
    (net (code "120") (name "unconnected-(LCD-DB1-Pad8)") (class "Default")
      (node (ref "LCD") (pin "8") (pinfunction "DB1_8") (pintype "bidirectional"))
    )
    (net (code "121") (name "unconnected-(LCD-DB2-Pad9)") (class "Default")
      (node (ref "LCD") (pin "9") (pinfunction "DB2_9") (pintype "bidirectional"))
    )
    (net (code "122") (name "unconnected-(LCD-DB3-Pad10)") (class "Default")
      (node (ref "LCD") (pin "10") (pinfunction "DB3_10") (pintype "bidirectional"))
    )
    (net (code "123") (name "unconnected-(OK1-VE-Pad7)") (class "Default")
      (node (ref "OK1") (pin "7") (pinfunction "VE_7") (pintype "passive"))
    )
    (net (code "124") (name "unconnected-(RN2-Pad7)") (class "Default")
      (node (ref "RN2") (pin "7") (pinfunction "7_7") (pintype "passive"))
    )
    (net (code "125") (name "unconnected-(RN2-Pad8)") (class "Default")
      (node (ref "RN2") (pin "8") (pinfunction "8_8") (pintype "passive"))
    )
    (net (code "126") (name "unconnected-(RN2-Pad9)") (class "Default")
      (node (ref "RN2") (pin "9") (pinfunction "9_9") (pintype "passive"))
    )
    (net (code "127") (name "unconnected-(RN3-Pad8)") (class "Default")
      (node (ref "RN3") (pin "8") (pinfunction "8_8") (pintype "passive"))
    )
    (net (code "128") (name "unconnected-(RN3-Pad9)") (class "Default")
      (node (ref "RN3") (pin "9") (pinfunction "9_9") (pintype "passive"))
    )
    (net (code "129") (name "unconnected-(X1-Pad1)") (class "Default")
      (node (ref "X1") (pin "1") (pinfunction "1_1") (pintype "passive"))
    )
    (net (code "130") (name "unconnected-(X1-Pad2)") (class "Default")
      (node (ref "X1") (pin "2") (pinfunction "2_2") (pintype "passive"))
    )
    (net (code "131") (name "unconnected-(X1-Pad3)") (class "Default")
      (node (ref "X1") (pin "3") (pinfunction "3_3") (pintype "passive"))
    )
    (net (code "132") (name "unconnected-(X2-Pad1)") (class "Default")
      (node (ref "X2") (pin "1") (pinfunction "1_1") (pintype "passive"))
    )
    (net (code "133") (name "unconnected-(X2-Pad3)") (class "Default")
      (node (ref "X2") (pin "3") (pinfunction "3_3") (pintype "passive"))
    )
  )
)
